# VHDCI_Carrier.net
KiCad netlist of a schematic drawn in Altium Designer
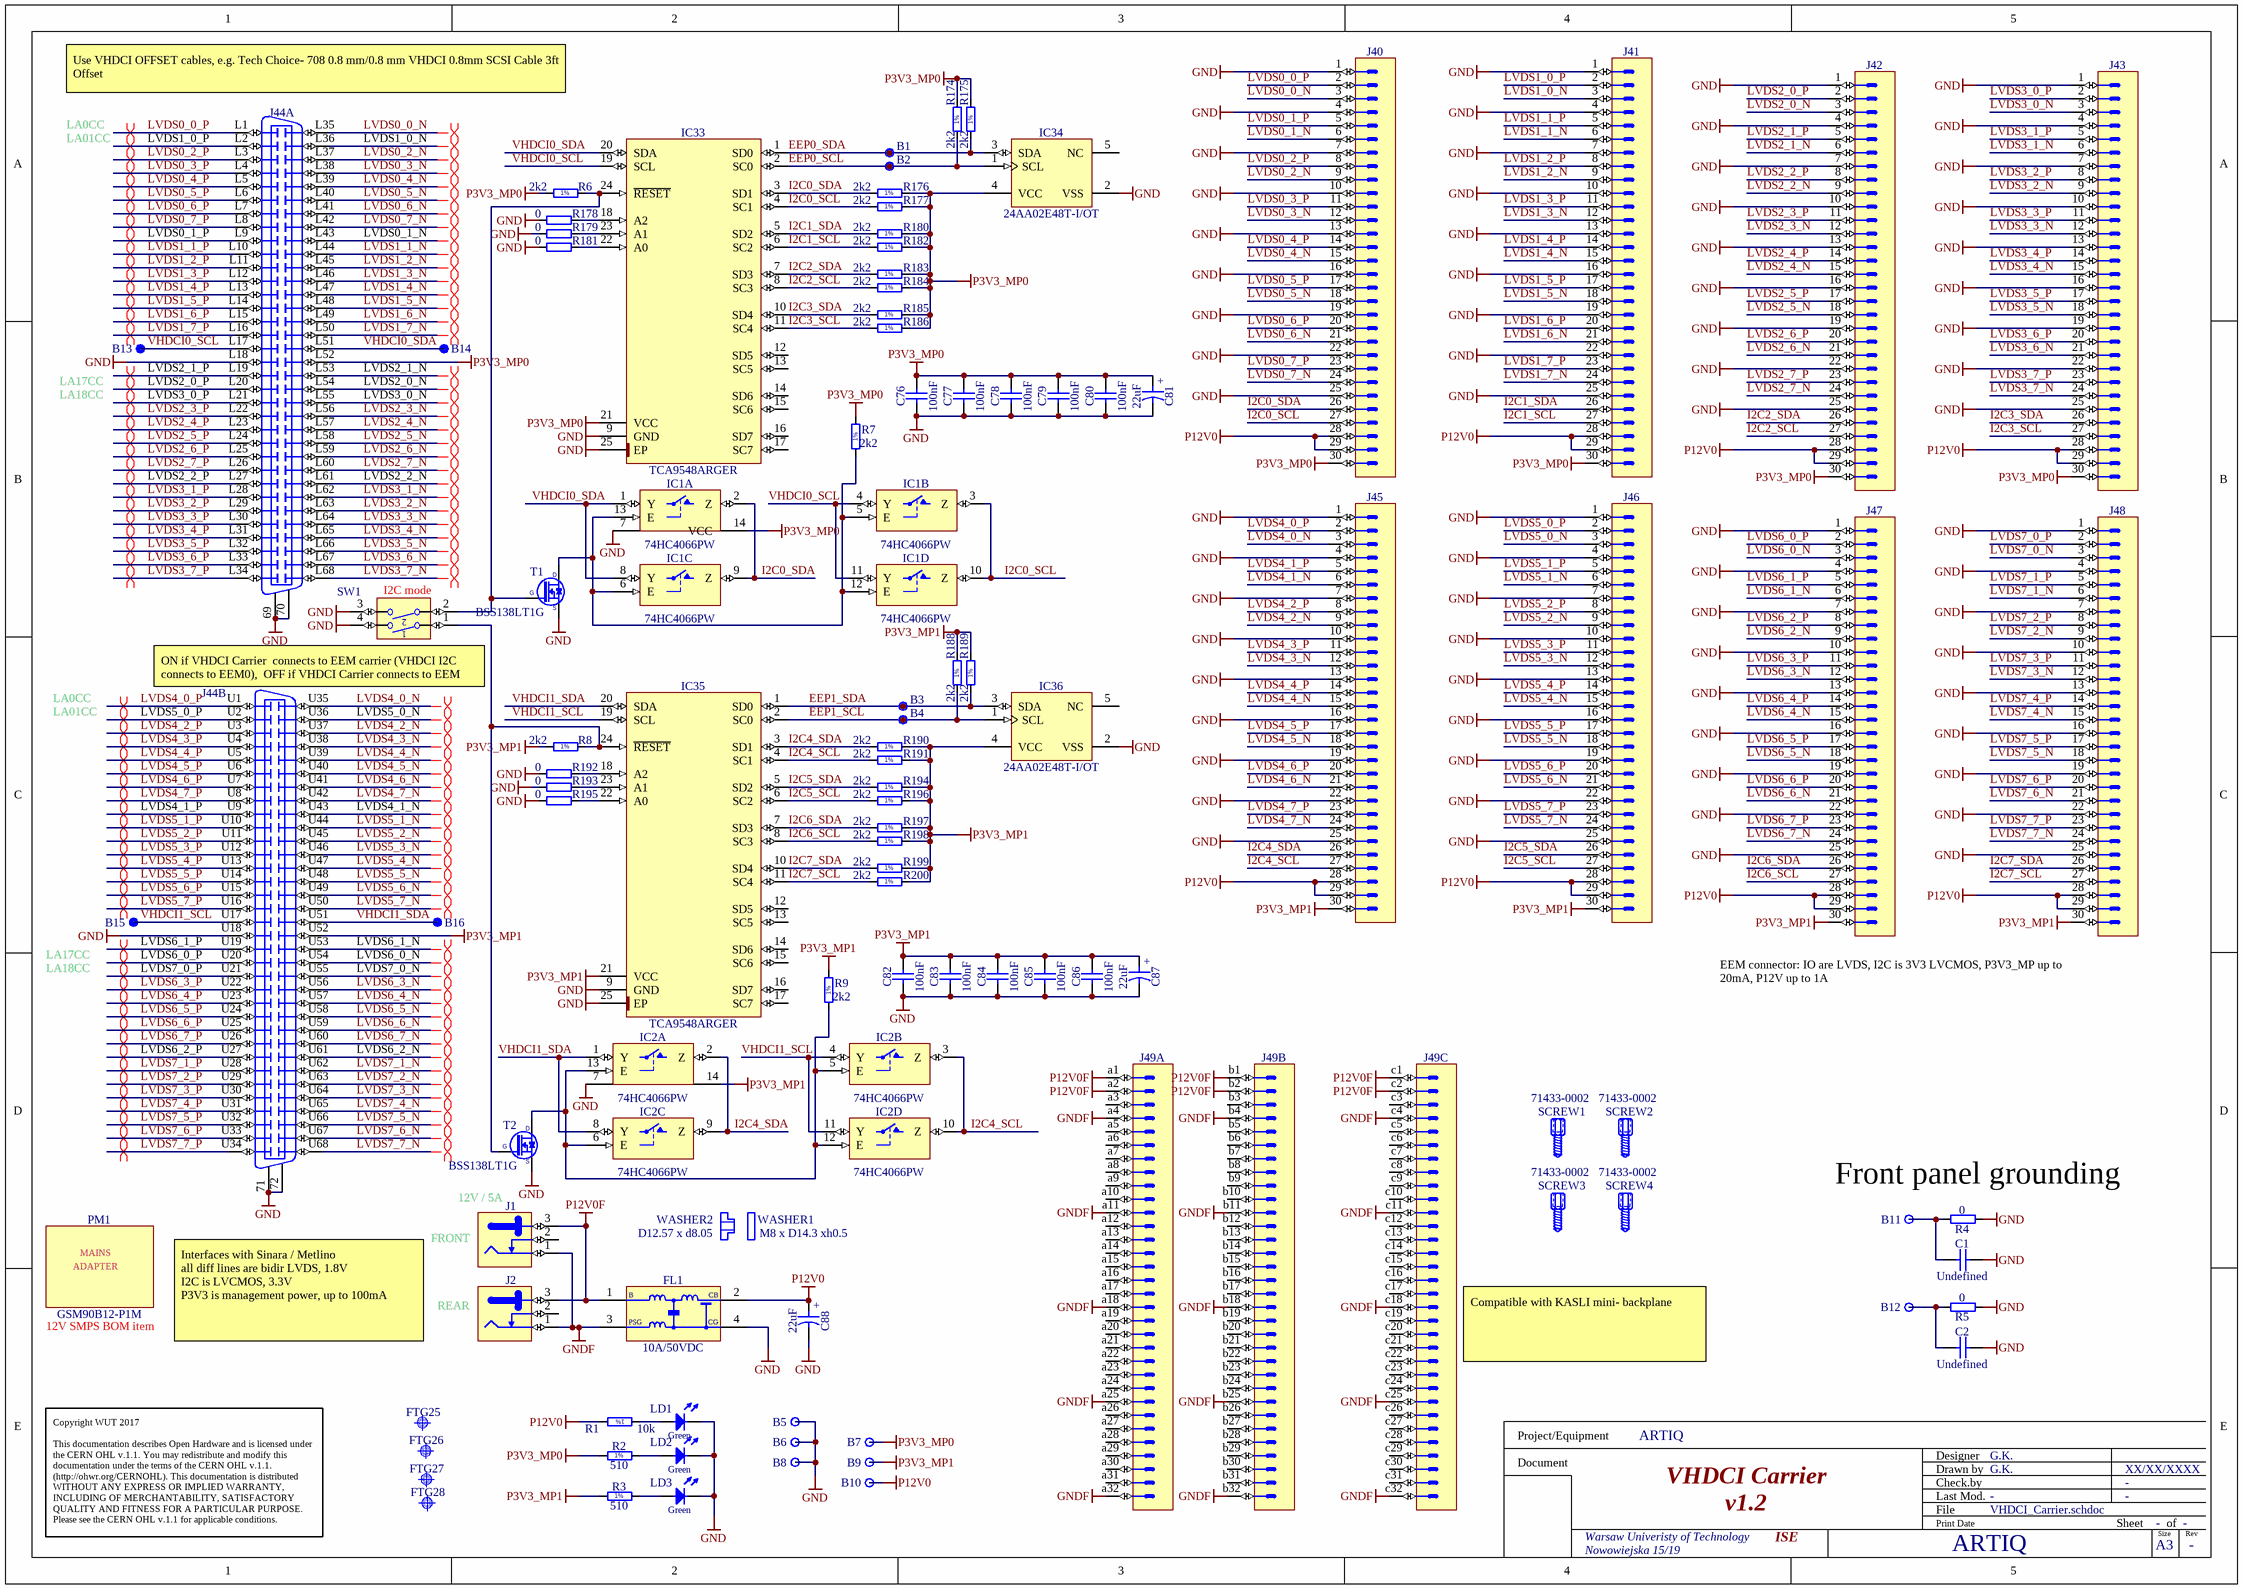
[diagram p0: VHDCI_Carrier.schdoc]

(export (version "E")
  (design (tool "Eeschema 10.0.6"))
  (components
    (comp (ref "B1")
      (value "SMD Pad")
      (footprint "C100")
      (description "Through Hole Pad")
      (fields (field (name "PART NUMBER") "SMD_PAD_D1MM") (field (name "AUTHOR") "CERN DEM JLC"))
      (libsource (lib "Eletro-mechanical") (part "Single SMD Pad (Round)"))
    )
    (comp (ref "B2")
      (value "SMD Pad")
      (footprint "C100")
      (description "Through Hole Pad")
      (fields (field (name "PART NUMBER") "SMD_PAD_D1MM") (field (name "AUTHOR") "CERN DEM JLC"))
      (libsource (lib "Eletro-mechanical") (part "Single SMD Pad (Round)"))
    )
    (comp (ref "B3")
      (value "SMD Pad")
      (footprint "C100")
      (description "Through Hole Pad")
      (fields (field (name "PART NUMBER") "SMD_PAD_D1MM") (field (name "AUTHOR") "CERN DEM JLC"))
      (libsource (lib "Eletro-mechanical") (part "Single SMD Pad (Round)"))
    )
    (comp (ref "B4")
      (value "SMD Pad")
      (footprint "C100")
      (description "Through Hole Pad")
      (fields (field (name "PART NUMBER") "SMD_PAD_D1MM") (field (name "AUTHOR") "CERN DEM JLC"))
      (libsource (lib "Eletro-mechanical") (part "Single SMD Pad (Round)"))
    )
    (comp (ref "B5")
      (value "Plated Hole")
      (footprint "c130h60")
      (description "Single Terminal Socket")
      (fields (field (name "PART NUMBER") "PLATED_HOLE0.6_PAD1.3") (field (name "AUTHOR") "CERN DEM MR"))
      (libsource (lib "Eletro-mechanical") (part "Single Terminal Socket"))
    )
    (comp (ref "B6")
      (value "Plated Hole")
      (footprint "c130h60")
      (description "Single Terminal Socket")
      (fields (field (name "PART NUMBER") "PLATED_HOLE0.6_PAD1.3") (field (name "AUTHOR") "CERN DEM MR"))
      (libsource (lib "Eletro-mechanical") (part "Single Terminal Socket"))
    )
    (comp (ref "B7")
      (value "Plated Hole")
      (footprint "c130h60")
      (description "Single Terminal Socket")
      (fields (field (name "PART NUMBER") "PLATED_HOLE0.6_PAD1.3") (field (name "AUTHOR") "CERN DEM MR"))
      (libsource (lib "Eletro-mechanical") (part "Single Terminal Socket"))
    )
    (comp (ref "B8")
      (value "Plated Hole")
      (footprint "c130h60")
      (description "Single Terminal Socket")
      (fields (field (name "PART NUMBER") "PLATED_HOLE0.6_PAD1.3") (field (name "AUTHOR") "CERN DEM MR"))
      (libsource (lib "Eletro-mechanical") (part "Single Terminal Socket"))
    )
    (comp (ref "B9")
      (value "Plated Hole")
      (footprint "c130h60")
      (description "Single Terminal Socket")
      (fields (field (name "PART NUMBER") "PLATED_HOLE0.6_PAD1.3") (field (name "AUTHOR") "CERN DEM MR"))
      (libsource (lib "Eletro-mechanical") (part "Single Terminal Socket"))
    )
    (comp (ref "B10")
      (value "Plated Hole")
      (footprint "c130h60")
      (description "Single Terminal Socket")
      (fields (field (name "PART NUMBER") "PLATED_HOLE0.6_PAD1.3") (field (name "AUTHOR") "CERN DEM MR"))
      (libsource (lib "Eletro-mechanical") (part "Single Terminal Socket"))
    )
    (comp (ref "B11")
      (value "Plated Hole")
      (footprint "MTG270_500")
      (description "Single Terminal Socket")
      (fields (field (name "PART NUMBER") "PLATED_HOLE2.7_PAD5.0") (field (name "AUTHOR") "CERN DEM JMW"))
      (libsource (lib "Eletro-mechanical") (part "Single Terminal Socket"))
    )
    (comp (ref "B12")
      (value "Plated Hole")
      (footprint "MTG270_500")
      (description "Single Terminal Socket")
      (fields (field (name "PART NUMBER") "PLATED_HOLE2.7_PAD5.0") (field (name "AUTHOR") "CERN DEM JMW"))
      (libsource (lib "Eletro-mechanical") (part "Single Terminal Socket"))
    )
    (comp (ref "B13")
      (value "SMD Pad")
      (footprint "C100")
      (description "Through Hole Pad")
      (fields (field (name "PART NUMBER") "SMD_PAD_D1MM") (field (name "AUTHOR") "CERN DEM JLC"))
      (libsource (lib "Eletro-mechanical") (part "Single SMD Pad (Round)"))
    )
    (comp (ref "B14")
      (value "SMD Pad")
      (footprint "C100")
      (description "Through Hole Pad")
      (fields (field (name "PART NUMBER") "SMD_PAD_D1MM") (field (name "AUTHOR") "CERN DEM JLC"))
      (libsource (lib "Eletro-mechanical") (part "Single SMD Pad (Round)"))
    )
    (comp (ref "B15")
      (value "SMD Pad")
      (footprint "C100")
      (description "Through Hole Pad")
      (fields (field (name "PART NUMBER") "SMD_PAD_D1MM") (field (name "AUTHOR") "CERN DEM JLC"))
      (libsource (lib "Eletro-mechanical") (part "Single SMD Pad (Round)"))
    )
    (comp (ref "B16")
      (value "SMD Pad")
      (footprint "C100")
      (description "Through Hole Pad")
      (fields (field (name "PART NUMBER") "SMD_PAD_D1MM") (field (name "AUTHOR") "CERN DEM JLC"))
      (libsource (lib "Eletro-mechanical") (part "Single SMD Pad (Round)"))
    )
    (comp (ref "C1")
      (value "Undefined")
      (footprint "CAPC2012X135N")
      (description "Non-polarised capacitor")
      (fields (field (name "PART NUMBER") "CC0805_NO-VALUE") (field (name "AUTHOR") "CERN DEM JLC"))
      (libsource (lib "Capacitors") (part "Capacitor - non polarized"))
    )
    (comp (ref "C2")
      (value "Undefined")
      (footprint "CAPC2012X135N")
      (description "Non-polarised capacitor")
      (fields (field (name "PART NUMBER") "CC0805_NO-VALUE") (field (name "AUTHOR") "CERN DEM JLC"))
      (libsource (lib "Capacitors") (part "Capacitor - non polarized"))
    )
    (comp (ref "C76")
      (value "100nF")
      (footprint "CAPC1005X55N")
      (description "Non-polarised capacitor")
      (fields
        (field (name "PART NUMBER") "CC0402_100NF_16V_10%_X5R")
        (field (name "VOLTAGE") "16V")
        (field (name "AUTHOR") "CERN DEM JLC")
      )
      (libsource (lib "Capacitors") (part "Capacitor - non polarized"))
    )
    (comp (ref "C77")
      (value "100nF")
      (footprint "CAPC1005X55N")
      (description "Non-polarised capacitor")
      (fields
        (field (name "PART NUMBER") "CC0402_100NF_16V_10%_X5R")
        (field (name "VOLTAGE") "16V")
        (field (name "AUTHOR") "CERN DEM JLC")
      )
      (libsource (lib "Capacitors") (part "Capacitor - non polarized"))
    )
    (comp (ref "C78")
      (value "100nF")
      (footprint "CAPC1005X55N")
      (description "Non-polarised capacitor")
      (fields
        (field (name "PART NUMBER") "CC0402_100NF_16V_10%_X5R")
        (field (name "VOLTAGE") "16V")
        (field (name "AUTHOR") "CERN DEM JLC")
      )
      (libsource (lib "Capacitors") (part "Capacitor - non polarized"))
    )
    (comp (ref "C79")
      (value "100nF")
      (footprint "CAPC1005X55N")
      (description "Non-polarised capacitor")
      (fields
        (field (name "PART NUMBER") "CC0402_100NF_16V_10%_X5R")
        (field (name "VOLTAGE") "16V")
        (field (name "AUTHOR") "CERN DEM JLC")
      )
      (libsource (lib "Capacitors") (part "Capacitor - non polarized"))
    )
    (comp (ref "C80")
      (value "100nF")
      (footprint "CAPC1005X55N")
      (description "Non-polarised capacitor")
      (fields
        (field (name "PART NUMBER") "CC0402_100NF_16V_10%_X5R")
        (field (name "VOLTAGE") "16V")
        (field (name "AUTHOR") "CERN DEM JLC")
      )
      (libsource (lib "Capacitors") (part "Capacitor - non polarized"))
    )
    (comp (ref "C81")
      (value "22uF")
      (footprint "CAPAE530X540N")
      (description "Polarised capacitor")
      (fields
        (field (name "PART NUMBER") "CAE530-540_22UF_16V_20%")
        (field (name "VOLTAGE") "16V")
        (field (name "AUTHOR") "CERN DEM JLC")
      )
      (libsource (lib "Capacitors") (part "Capacitor - polarized"))
    )
    (comp (ref "C82")
      (value "100nF")
      (footprint "CAPC1005X55N")
      (description "Non-polarised capacitor")
      (fields
        (field (name "PART NUMBER") "CC0402_100NF_16V_10%_X5R")
        (field (name "VOLTAGE") "16V")
        (field (name "AUTHOR") "CERN DEM JLC")
      )
      (libsource (lib "Capacitors") (part "Capacitor - non polarized"))
    )
    (comp (ref "C83")
      (value "100nF")
      (footprint "CAPC1005X55N")
      (description "Non-polarised capacitor")
      (fields
        (field (name "PART NUMBER") "CC0402_100NF_16V_10%_X5R")
        (field (name "VOLTAGE") "16V")
        (field (name "AUTHOR") "CERN DEM JLC")
      )
      (libsource (lib "Capacitors") (part "Capacitor - non polarized"))
    )
    (comp (ref "C84")
      (value "100nF")
      (footprint "CAPC1005X55N")
      (description "Non-polarised capacitor")
      (fields
        (field (name "PART NUMBER") "CC0402_100NF_16V_10%_X5R")
        (field (name "VOLTAGE") "16V")
        (field (name "AUTHOR") "CERN DEM JLC")
      )
      (libsource (lib "Capacitors") (part "Capacitor - non polarized"))
    )
    (comp (ref "C85")
      (value "100nF")
      (footprint "CAPC1005X55N")
      (description "Non-polarised capacitor")
      (fields
        (field (name "PART NUMBER") "CC0402_100NF_16V_10%_X5R")
        (field (name "VOLTAGE") "16V")
        (field (name "AUTHOR") "CERN DEM JLC")
      )
      (libsource (lib "Capacitors") (part "Capacitor - non polarized"))
    )
    (comp (ref "C86")
      (value "100nF")
      (footprint "CAPC1005X55N")
      (description "Non-polarised capacitor")
      (fields
        (field (name "PART NUMBER") "CC0402_100NF_16V_10%_X5R")
        (field (name "VOLTAGE") "16V")
        (field (name "AUTHOR") "CERN DEM JLC")
      )
      (libsource (lib "Capacitors") (part "Capacitor - non polarized"))
    )
    (comp (ref "C87")
      (value "22uF")
      (footprint "CAPAE530X540N")
      (description "Polarised capacitor")
      (fields
        (field (name "PART NUMBER") "CAE530-540_22UF_16V_20%")
        (field (name "VOLTAGE") "16V")
        (field (name "AUTHOR") "CERN DEM JLC")
      )
      (libsource (lib "Capacitors") (part "Capacitor - polarized"))
    )
    (comp (ref "C88")
      (value "22uF")
      (footprint "CAPAE530X540N")
      (description "Polarised capacitor")
      (fields
        (field (name "PART NUMBER") "CAE530-540_22UF_16V_20%")
        (field (name "VOLTAGE") "16V")
        (field (name "AUTHOR") "CERN DEM JLC")
      )
      (libsource (lib "Capacitors") (part "Capacitor - polarized"))
    )
    (comp (ref "FL1")
      (value "10A/50VDC")
      (footprint "FIL_MURATA_BNX02")
      (description "Block Type EMIFIL (LC Combined)")
      (fields
        (field (name "PART NUMBER") "FIL_MURATA_BNX022-01L")
        (field (name "MANUFACTURER") "MURATA")
        (field (name "AUTHOR") "CERN DEM JLC")
      )
      (libsource (lib "Inductors & Transformers") (part "FIL_MURATA_BNX02"))
    )
    (comp (ref "FTG25")
      (value "Use only in PCB")
      (footprint "FIDUCIAL_TOP_C100-200")
      (description "Fiducial Target")
      (fields (field (name "PART NUMBER") "FIDUCIAL_TARGET_C100-200") (field (name "AUTHOR") "CERN DEM JLC"))
      (libsource (lib "Eletro-mechanical") (part "Fiducial Target"))
    )
    (comp (ref "FTG26")
      (value "Use only in PCB")
      (footprint "FIDUCIAL_TOP_S100-200")
      (description "Fiducial Target")
      (fields (field (name "PART NUMBER") "FIDUCIAL_TARGET_S100-200") (field (name "AUTHOR") "CERN DEM JLC"))
      (libsource (lib "Eletro-mechanical") (part "Fiducial Target"))
    )
    (comp (ref "FTG27")
      (value "Use only in PCB")
      (footprint "FIDUCIAL_TOP_S200-400")
      (description "Fiducial Target")
      (fields (field (name "PART NUMBER") "FIDUCIAL_TARGET_S200-400") (field (name "AUTHOR") "CERN DEM JLC"))
      (libsource (lib "Eletro-mechanical") (part "Fiducial Target"))
    )
    (comp (ref "FTG28")
      (value "Use only in PCB")
      (footprint "FIDUCIAL_TOP_S100-200")
      (description "Fiducial Target")
      (fields (field (name "PART NUMBER") "FIDUCIAL_TARGET_S100-200") (field (name "AUTHOR") "CERN DEM JLC"))
      (libsource (lib "Eletro-mechanical") (part "Fiducial Target"))
    )
    (comp (ref "IC1")
      (value "74HC4066PW")
      (footprint "SOP65P640X110-14N")
      (fields (field (name "MANUFACTURER") "NXP SEMICONDUCTORS") (field (name "AUTHOR") "CERN DEM JLC"))
      (libsource (lib "") (part "4066_1"))
    )
    (comp (ref "IC2")
      (value "74HC4066PW")
      (footprint "SOP65P640X110-14N")
      (fields (field (name "MANUFACTURER") "NXP SEMICONDUCTORS") (field (name "AUTHOR") "CERN DEM JLC"))
      (libsource (lib "ICs And Semiconductors") (part "4066"))
    )
    (comp (ref "IC33")
      (value "TCA9548ARGER")
      (footprint "QFN50P400X400X100-25N-S220")
      (description "Low Voltage 8-Channel I2C Switch With Reset")
      (fields (field (name "MANUFACTURER") "TEXAS INSTRUMENTS") (field (name "AUTHOR") "CERN DEM JLC"))
      (libsource (lib "ICs And Semiconductors") (part "TCA9548ARGER"))
    )
    (comp (ref "IC34")
      (value "24AA02E48T-I/OT")
      (footprint "SOT95P280X145-5N")
      (description "1.7V-5.5V, 2K I2C Serial EEPROM With EUI-48 Node Identity")
      (fields (field (name "MANUFACTURER") "MICROCHIP TECHNOLOGY") (field (name "AUTHOR") "CERN DEM MR"))
      (libsource (lib "ICs And Semiconductors") (part "24AA02E48T-I/OT"))
    )
    (comp (ref "IC35")
      (value "TCA9548ARGER")
      (footprint "QFN50P400X400X100-25N-S220")
      (description "Low Voltage 8-Channel I2C Switch With Reset")
      (fields (field (name "MANUFACTURER") "TEXAS INSTRUMENTS") (field (name "AUTHOR") "CERN DEM JLC"))
      (libsource (lib "ICs And Semiconductors") (part "TCA9548ARGER"))
    )
    (comp (ref "IC36")
      (value "24AA02E48T-I/OT")
      (footprint "SOT95P280X145-5N")
      (description "1.7V-5.5V, 2K I2C Serial EEPROM With EUI-48 Node Identity")
      (fields (field (name "MANUFACTURER") "MICROCHIP TECHNOLOGY") (field (name "AUTHOR") "CERN DEM MR"))
      (libsource (lib "ICs And Semiconductors") (part "24AA02E48T-I/OT"))
    )
    (comp (ref "J1")
      (value "Jack")
      (footprint "SWITCHCRAFT_L712RA")
      (description "24V /3. 5A, 2.1mm Diameter Pin, SMD DC Power Supply Connector With  Break Contact")
      (fields
        (field (name "PART NUMBER") "SWITCHCRAFT_L712RA")
        (field (name "MANUFACTURER") "SWITCHCRAFT")
        (field (name "AUTHOR") "GK")
      )
      (libsource (lib "LIBRARY_SCH") (part "CON_DC_5A_THT_RA"))
    )
    (comp (ref "J2")
      (value "Jack")
      (footprint "SWITCHCRAFT_L712RA")
      (description "24V /3. 5A, 2.1mm Diameter Pin, SMD DC Power Supply Connector With  Break Contact")
      (fields
        (field (name "PART NUMBER") "SWITCHCRAFT_L712RA")
        (field (name "MANUFACTURER") "SWITCHCRAFT")
        (field (name "AUTHOR") "GK")
      )
      (libsource (lib "LIBRARY_SCH") (part "CON_DC_5A_THT_RA"))
    )
    (comp (ref "J40")
      (value "~")
      (footprint "3M_N2530-6002RB")
      (description "Connector 30 Male")
      (fields
        (field (name "PART NUMBER") "3M_N2530-6002RB")
        (field (name "MANUFACTURER") "3M")
        (field (name "AUTHOR") "CERN DEM JLC")
      )
      (libsource (lib "Connectors") (part "Connector 30 Male"))
    )
    (comp (ref "J41")
      (value "~")
      (footprint "3M_N2530-6002RB")
      (description "Connector 30 Male")
      (fields
        (field (name "PART NUMBER") "3M_N2530-6002RB")
        (field (name "MANUFACTURER") "3M")
        (field (name "AUTHOR") "CERN DEM JLC")
      )
      (libsource (lib "Connectors") (part "Connector 30 Male"))
    )
    (comp (ref "J42")
      (value "~")
      (footprint "3M_N2530-6002RB")
      (description "Connector 30 Male")
      (fields
        (field (name "PART NUMBER") "3M_N2530-6002RB")
        (field (name "MANUFACTURER") "3M")
        (field (name "AUTHOR") "CERN DEM JLC")
      )
      (libsource (lib "Connectors") (part "Connector 30 Male"))
    )
    (comp (ref "J43")
      (value "~")
      (footprint "3M_N2530-6002RB")
      (description "Connector 30 Male")
      (fields
        (field (name "PART NUMBER") "3M_N2530-6002RB")
        (field (name "MANUFACTURER") "3M")
        (field (name "AUTHOR") "CERN DEM JLC")
      )
      (libsource (lib "Connectors") (part "Connector 30 Male"))
    )
    (comp (ref "J44")
      (value "VHDCI")
      (footprint "MOLEX_74337-0015")
      (description "Very High Density Cable Interconnect (VHDCI ) 2x68 Female")
      (fields
        (field (name "PART NUMBER") "Delivered by GK")
        (field (name "MANUFACTURER") "MOLEX")
        (field (name "AUTHOR") "CERN DEM JLC")
      )
      (libsource (lib "Connectors") (part "Connector VHDCI 2x68 Female"))
    )
    (comp (ref "J45")
      (value "~")
      (footprint "3M_N2530-6002RB")
      (description "Connector 30 Male")
      (fields
        (field (name "PART NUMBER") "3M_N2530-6002RB")
        (field (name "MANUFACTURER") "3M")
        (field (name "AUTHOR") "CERN DEM JLC")
      )
      (libsource (lib "Connectors") (part "Connector 30 Male"))
    )
    (comp (ref "J46")
      (value "~")
      (footprint "3M_N2530-6002RB")
      (description "Connector 30 Male")
      (fields
        (field (name "PART NUMBER") "3M_N2530-6002RB")
        (field (name "MANUFACTURER") "3M")
        (field (name "AUTHOR") "CERN DEM JLC")
      )
      (libsource (lib "Connectors") (part "Connector 30 Male"))
    )
    (comp (ref "J47")
      (value "~")
      (footprint "3M_N2530-6002RB")
      (description "Connector 30 Male")
      (fields
        (field (name "PART NUMBER") "3M_N2530-6002RB")
        (field (name "MANUFACTURER") "3M")
        (field (name "AUTHOR") "CERN DEM JLC")
      )
      (libsource (lib "Connectors") (part "Connector 30 Male"))
    )
    (comp (ref "J48")
      (value "~")
      (footprint "3M_N2530-6002RB")
      (description "Connector 30 Male")
      (fields
        (field (name "PART NUMBER") "3M_N2530-6002RB")
        (field (name "MANUFACTURER") "3M")
        (field (name "AUTHOR") "CERN DEM JLC")
      )
      (libsource (lib "Connectors") (part "Connector 30 Male"))
    )
    (comp (ref "J49")
      (value "DNP")
      (footprint "HARTING_09 03 196 2921")
      (description "Connector 96abc male (3x32)")
      (fields
        (field (name "PART NUMBER") "HARTING_09 03 196 2921")
        (field (name "MANUFACTURER") "HARTING")
        (field (name "AUTHOR") "CERN DEM JLC")
      )
      (libsource (lib "Connectors") (part "Connector 96abc male (3x32)"))
    )
    (comp (ref "LD1")
      (value "Green")
      (footprint "LED_KINGBRIGHT_KPH-1608CGCK")
      (description "LED Green 1C 2A")
      (fields
        (field (name "PART NUMBER") "LED_KINGBRIGHT_KPH-1608CGCK")
        (field (name "MANUFACTURER") "KINGBRIGHT")
        (field (name "AUTHOR") "CERN DEM JLC")
      )
      (libsource (lib "ICs And Semiconductors") (part "LED Green 1C 2A"))
    )
    (comp (ref "LD2")
      (value "Green")
      (footprint "LED_KINGBRIGHT_KPH-1608CGCK")
      (description "LED Green 1C 2A")
      (fields
        (field (name "PART NUMBER") "LED_KINGBRIGHT_KPH-1608CGCK")
        (field (name "MANUFACTURER") "KINGBRIGHT")
        (field (name "AUTHOR") "CERN DEM JLC")
      )
      (libsource (lib "ICs And Semiconductors") (part "LED Green 1C 2A"))
    )
    (comp (ref "LD3")
      (value "Green")
      (footprint "LED_KINGBRIGHT_KPH-1608CGCK")
      (description "LED Green 1C 2A")
      (fields
        (field (name "PART NUMBER") "LED_KINGBRIGHT_KPH-1608CGCK")
        (field (name "MANUFACTURER") "KINGBRIGHT")
        (field (name "AUTHOR") "CERN DEM JLC")
      )
      (libsource (lib "ICs And Semiconductors") (part "LED Green 1C 2A"))
    )
    (comp (ref "PM1")
      (value "GSM90B12-P1M")
      (footprint "DC_DC_GSM90B12-P1M")
      (description "90W  AC-DC  Medical Power Adaptor")
      (fields (field (name "MANUFACTURER") "MEAN WELL") (field (name "AUTHOR") "GK"))
      (libsource (lib "LIBRARY_SCH") (part "DC_DC_GSM90B12-P1M"))
    )
    (comp (ref "R1")
      (value "10k")
      (footprint "RESC1005X40N")
      (description "Resistor - 1%")
      (fields
        (field (name "PART NUMBER") "R0402_10K_1%_0.0625W_100PPM")
        (field (name "POWER") "0.0625W")
        (field (name "AUTHOR") "CERN DEM JLC")
      )
      (libsource (lib "Resistors") (part "Resistor - 1%"))
    )
    (comp (ref "R2")
      (value "510")
      (footprint "RESC1005X40N")
      (description "Resistor - 1%")
      (fields
        (field (name "PART NUMBER") "R0402_510R_1%_0.0625W_100PPM")
        (field (name "POWER") "0.0625W")
        (field (name "AUTHOR") "CERN DEM JLC")
      )
      (libsource (lib "Resistors") (part "Resistor - 1%"))
    )
    (comp (ref "R3")
      (value "510")
      (footprint "RESC1005X40N")
      (description "Resistor - 1%")
      (fields
        (field (name "PART NUMBER") "R0402_510R_1%_0.0625W_100PPM")
        (field (name "POWER") "0.0625W")
        (field (name "AUTHOR") "CERN DEM JLC")
      )
      (libsource (lib "Resistors") (part "Resistor - 1%"))
    )
    (comp (ref "R4")
      (value "0")
      (footprint "RESC1608X55N")
      (description "Resistor")
      (fields
        (field (name "PART NUMBER") "R0603_0R_JUMPER")
        (field (name "MANUFACTURER") "GENERIC")
        (field (name "AUTHOR") "CERN DEM JLC")
      )
      (libsource (lib "Resistors") (part "Resistor"))
    )
    (comp (ref "R5")
      (value "0")
      (footprint "RESC1608X55N")
      (description "Resistor")
      (fields
        (field (name "PART NUMBER") "R0603_0R_JUMPER")
        (field (name "MANUFACTURER") "GENERIC")
        (field (name "AUTHOR") "CERN DEM JLC")
      )
      (libsource (lib "Resistors") (part "Resistor"))
    )
    (comp (ref "R6")
      (value "2k2")
      (footprint "RESC1005X40N")
      (description "Resistor - 1%")
      (fields
        (field (name "PART NUMBER") "R0402_2K2_1%_0.0625W_100PPM")
        (field (name "POWER") "0.0625W")
        (field (name "AUTHOR") "CERN DEM JLC")
      )
      (libsource (lib "Resistors") (part "Resistor - 1%"))
    )
    (comp (ref "R7")
      (value "2k2")
      (footprint "RESC1005X40N")
      (description "Resistor - 1%")
      (fields
        (field (name "PART NUMBER") "R0402_2K2_1%_0.0625W_100PPM")
        (field (name "POWER") "0.0625W")
        (field (name "AUTHOR") "CERN DEM JLC")
      )
      (libsource (lib "Resistors") (part "Resistor - 1%"))
    )
    (comp (ref "R8")
      (value "2k2")
      (footprint "RESC1005X40N")
      (description "Resistor - 1%")
      (fields
        (field (name "PART NUMBER") "R0402_2K2_1%_0.0625W_100PPM")
        (field (name "POWER") "0.0625W")
        (field (name "AUTHOR") "CERN DEM JLC")
      )
      (libsource (lib "Resistors") (part "Resistor - 1%"))
    )
    (comp (ref "R9")
      (value "2k2")
      (footprint "RESC1005X40N")
      (description "Resistor - 1%")
      (fields
        (field (name "PART NUMBER") "R0402_2K2_1%_0.0625W_100PPM")
        (field (name "POWER") "0.0625W")
        (field (name "AUTHOR") "CERN DEM JLC")
      )
      (libsource (lib "Resistors") (part "Resistor - 1%"))
    )
    (comp (ref "R174")
      (value "2k2")
      (footprint "RESC1005X40N")
      (description "Resistor - 1%")
      (fields
        (field (name "PART NUMBER") "R0402_2K2_1%_0.0625W_100PPM")
        (field (name "POWER") "0.0625W")
        (field (name "AUTHOR") "CERN DEM JLC")
      )
      (libsource (lib "Resistors") (part "Resistor - 1%"))
    )
    (comp (ref "R175")
      (value "2k2")
      (footprint "RESC1005X40N")
      (description "Resistor - 1%")
      (fields
        (field (name "PART NUMBER") "R0402_2K2_1%_0.0625W_100PPM")
        (field (name "POWER") "0.0625W")
        (field (name "AUTHOR") "CERN DEM JLC")
      )
      (libsource (lib "Resistors") (part "Resistor - 1%"))
    )
    (comp (ref "R176")
      (value "2k2")
      (footprint "RESC1005X40N")
      (description "Resistor - 1%")
      (fields
        (field (name "PART NUMBER") "R0402_2K2_1%_0.0625W_100PPM")
        (field (name "POWER") "0.0625W")
        (field (name "AUTHOR") "CERN DEM JLC")
      )
      (libsource (lib "Resistors") (part "Resistor - 1%"))
    )
    (comp (ref "R177")
      (value "2k2")
      (footprint "RESC1005X40N")
      (description "Resistor - 1%")
      (fields
        (field (name "PART NUMBER") "R0402_2K2_1%_0.0625W_100PPM")
        (field (name "POWER") "0.0625W")
        (field (name "AUTHOR") "CERN DEM JLC")
      )
      (libsource (lib "Resistors") (part "Resistor - 1%"))
    )
    (comp (ref "R178")
      (value "0")
      (footprint "RESC1005X40N")
      (description "Resistor")
      (fields
        (field (name "PART NUMBER") "R0402_0R_JUMPER")
        (field (name "MANUFACTURER") "GENERIC")
        (field (name "AUTHOR") "CERN DEM JLC")
      )
      (libsource (lib "Resistors") (part "Resistor"))
    )
    (comp (ref "R179")
      (value "0")
      (footprint "RESC1005X40N")
      (description "Resistor")
      (fields
        (field (name "PART NUMBER") "R0402_0R_JUMPER")
        (field (name "MANUFACTURER") "GENERIC")
        (field (name "AUTHOR") "CERN DEM JLC")
      )
      (libsource (lib "Resistors") (part "Resistor"))
    )
    (comp (ref "R180")
      (value "2k2")
      (footprint "RESC1005X40N")
      (description "Resistor - 1%")
      (fields
        (field (name "PART NUMBER") "R0402_2K2_1%_0.0625W_100PPM")
        (field (name "POWER") "0.0625W")
        (field (name "AUTHOR") "CERN DEM JLC")
      )
      (libsource (lib "Resistors") (part "Resistor - 1%"))
    )
    (comp (ref "R181")
      (value "0")
      (footprint "RESC1005X40N")
      (description "Resistor")
      (fields
        (field (name "PART NUMBER") "R0402_0R_JUMPER")
        (field (name "MANUFACTURER") "GENERIC")
        (field (name "AUTHOR") "CERN DEM JLC")
      )
      (libsource (lib "Resistors") (part "Resistor"))
    )
    (comp (ref "R182")
      (value "2k2")
      (footprint "RESC1005X40N")
      (description "Resistor - 1%")
      (fields
        (field (name "PART NUMBER") "R0402_2K2_1%_0.0625W_100PPM")
        (field (name "POWER") "0.0625W")
        (field (name "AUTHOR") "CERN DEM JLC")
      )
      (libsource (lib "Resistors") (part "Resistor - 1%"))
    )
    (comp (ref "R183")
      (value "2k2")
      (footprint "RESC1005X40N")
      (description "Resistor - 1%")
      (fields
        (field (name "PART NUMBER") "R0402_2K2_1%_0.0625W_100PPM")
        (field (name "POWER") "0.0625W")
        (field (name "AUTHOR") "CERN DEM JLC")
      )
      (libsource (lib "Resistors") (part "Resistor - 1%"))
    )
    (comp (ref "R184")
      (value "2k2")
      (footprint "RESC1005X40N")
      (description "Resistor - 1%")
      (fields
        (field (name "PART NUMBER") "R0402_2K2_1%_0.0625W_100PPM")
        (field (name "POWER") "0.0625W")
        (field (name "AUTHOR") "CERN DEM JLC")
      )
      (libsource (lib "Resistors") (part "Resistor - 1%"))
    )
    (comp (ref "R185")
      (value "2k2")
      (footprint "RESC1005X40N")
      (description "Resistor - 1%")
      (fields
        (field (name "PART NUMBER") "R0402_2K2_1%_0.0625W_100PPM")
        (field (name "POWER") "0.0625W")
        (field (name "AUTHOR") "CERN DEM JLC")
      )
      (libsource (lib "Resistors") (part "Resistor - 1%"))
    )
    (comp (ref "R186")
      (value "2k2")
      (footprint "RESC1005X40N")
      (description "Resistor - 1%")
      (fields
        (field (name "PART NUMBER") "R0402_2K2_1%_0.0625W_100PPM")
        (field (name "POWER") "0.0625W")
        (field (name "AUTHOR") "CERN DEM JLC")
      )
      (libsource (lib "Resistors") (part "Resistor - 1%"))
    )
    (comp (ref "R188")
      (value "2k2")
      (footprint "RESC1005X40N")
      (description "Resistor - 1%")
      (fields
        (field (name "PART NUMBER") "R0402_2K2_1%_0.0625W_100PPM")
        (field (name "POWER") "0.0625W")
        (field (name "AUTHOR") "CERN DEM JLC")
      )
      (libsource (lib "Resistors") (part "Resistor - 1%"))
    )
    (comp (ref "R189")
      (value "2k2")
      (footprint "RESC1005X40N")
      (description "Resistor - 1%")
      (fields
        (field (name "PART NUMBER") "R0402_2K2_1%_0.0625W_100PPM")
        (field (name "POWER") "0.0625W")
        (field (name "AUTHOR") "CERN DEM JLC")
      )
      (libsource (lib "Resistors") (part "Resistor - 1%"))
    )
    (comp (ref "R190")
      (value "2k2")
      (footprint "RESC1005X40N")
      (description "Resistor - 1%")
      (fields
        (field (name "PART NUMBER") "R0402_2K2_1%_0.0625W_100PPM")
        (field (name "POWER") "0.0625W")
        (field (name "AUTHOR") "CERN DEM JLC")
      )
      (libsource (lib "Resistors") (part "Resistor - 1%"))
    )
    (comp (ref "R191")
      (value "2k2")
      (footprint "RESC1005X40N")
      (description "Resistor - 1%")
      (fields
        (field (name "PART NUMBER") "R0402_2K2_1%_0.0625W_100PPM")
        (field (name "POWER") "0.0625W")
        (field (name "AUTHOR") "CERN DEM JLC")
      )
      (libsource (lib "Resistors") (part "Resistor - 1%"))
    )
    (comp (ref "R192")
      (value "0")
      (footprint "RESC1005X40N")
      (description "Resistor")
      (fields
        (field (name "PART NUMBER") "R0402_0R_JUMPER")
        (field (name "MANUFACTURER") "GENERIC")
        (field (name "AUTHOR") "CERN DEM JLC")
      )
      (libsource (lib "Resistors") (part "Resistor"))
    )
    (comp (ref "R193")
      (value "0")
      (footprint "RESC1005X40N")
      (description "Resistor")
      (fields
        (field (name "PART NUMBER") "R0402_0R_JUMPER")
        (field (name "MANUFACTURER") "GENERIC")
        (field (name "AUTHOR") "CERN DEM JLC")
      )
      (libsource (lib "Resistors") (part "Resistor"))
    )
    (comp (ref "R194")
      (value "2k2")
      (footprint "RESC1005X40N")
      (description "Resistor - 1%")
      (fields
        (field (name "PART NUMBER") "R0402_2K2_1%_0.0625W_100PPM")
        (field (name "POWER") "0.0625W")
        (field (name "AUTHOR") "CERN DEM JLC")
      )
      (libsource (lib "Resistors") (part "Resistor - 1%"))
    )
    (comp (ref "R195")
      (value "0")
      (footprint "RESC1005X40N")
      (description "Resistor")
      (fields
        (field (name "PART NUMBER") "R0402_0R_JUMPER")
        (field (name "MANUFACTURER") "GENERIC")
        (field (name "AUTHOR") "CERN DEM JLC")
      )
      (libsource (lib "Resistors") (part "Resistor"))
    )
    (comp (ref "R196")
      (value "2k2")
      (footprint "RESC1005X40N")
      (description "Resistor - 1%")
      (fields
        (field (name "PART NUMBER") "R0402_2K2_1%_0.0625W_100PPM")
        (field (name "POWER") "0.0625W")
        (field (name "AUTHOR") "CERN DEM JLC")
      )
      (libsource (lib "Resistors") (part "Resistor - 1%"))
    )
    (comp (ref "R197")
      (value "2k2")
      (footprint "RESC1005X40N")
      (description "Resistor - 1%")
      (fields
        (field (name "PART NUMBER") "R0402_2K2_1%_0.0625W_100PPM")
        (field (name "POWER") "0.0625W")
        (field (name "AUTHOR") "CERN DEM JLC")
      )
      (libsource (lib "Resistors") (part "Resistor - 1%"))
    )
    (comp (ref "R198")
      (value "2k2")
      (footprint "RESC1005X40N")
      (description "Resistor - 1%")
      (fields
        (field (name "PART NUMBER") "R0402_2K2_1%_0.0625W_100PPM")
        (field (name "POWER") "0.0625W")
        (field (name "AUTHOR") "CERN DEM JLC")
      )
      (libsource (lib "Resistors") (part "Resistor - 1%"))
    )
    (comp (ref "R199")
      (value "2k2")
      (footprint "RESC1005X40N")
      (description "Resistor - 1%")
      (fields
        (field (name "PART NUMBER") "R0402_2K2_1%_0.0625W_100PPM")
        (field (name "POWER") "0.0625W")
        (field (name "AUTHOR") "CERN DEM JLC")
      )
      (libsource (lib "Resistors") (part "Resistor - 1%"))
    )
    (comp (ref "R200")
      (value "2k2")
      (footprint "RESC1005X40N")
      (description "Resistor - 1%")
      (fields
        (field (name "PART NUMBER") "R0402_2K2_1%_0.0625W_100PPM")
        (field (name "POWER") "0.0625W")
        (field (name "AUTHOR") "CERN DEM JLC")
      )
      (libsource (lib "Resistors") (part "Resistor - 1%"))
    )
    (comp (ref "SCREW1")
      (value "71433-0002")
      (footprint "MOLEX_71433-0002")
      (description "VHDCI Female Screw Lock")
      (fields
        (field (name "PART NUMBER") "MOLEX_71433-0002")
        (field (name "MANUFACTURER") "Molex")
        (field (name "AUTHOR") "GK")
      )
      (libsource (lib "LIBRARY_SCH") (part "MECH_VHDCI_screw_lock"))
    )
    (comp (ref "SCREW2")
      (value "71433-0002")
      (footprint "MOLEX_71433-0002")
      (description "VHDCI Female Screw Lock")
      (fields
        (field (name "PART NUMBER") "MOLEX_71433-0002")
        (field (name "MANUFACTURER") "Molex")
        (field (name "AUTHOR") "GK")
      )
      (libsource (lib "LIBRARY_SCH") (part "MECH_VHDCI_screw_lock"))
    )
    (comp (ref "SCREW3")
      (value "71433-0002")
      (footprint "MOLEX_71433-0002")
      (description "VHDCI Female Screw Lock")
      (fields
        (field (name "PART NUMBER") "MOLEX_71433-0002")
        (field (name "MANUFACTURER") "Molex")
        (field (name "AUTHOR") "GK")
      )
      (libsource (lib "LIBRARY_SCH") (part "MECH_VHDCI_screw_lock"))
    )
    (comp (ref "SCREW4")
      (value "71433-0002")
      (footprint "MOLEX_71433-0002")
      (description "VHDCI Female Screw Lock")
      (fields
        (field (name "PART NUMBER") "MOLEX_71433-0002")
        (field (name "MANUFACTURER") "Molex")
        (field (name "AUTHOR") "GK")
      )
      (libsource (lib "LIBRARY_SCH") (part "MECH_VHDCI_screw_lock"))
    )
    (comp (ref "SW1")
      (value "Switch")
      (footprint "SW_TYCO_1571983-1")
      (description "2 Ways SPST DIP Switch")
      (fields
        (field (name "PART NUMBER") "SW_TYCO_1571983-1")
        (field (name "MANUFACTURER") "TYCO")
        (field (name "AUTHOR") "CERN DEM JLC")
      )
      (libsource (lib "Eletro-mechanical") (part "SW 2x SPST DIP Switch"))
    )
    (comp (ref "T1")
      (value "BSS138LT1G")
      (footprint "SOT95P240X110-3N")
      (description "N-CHANNEL MOSFET WITH DIODE")
      (fields (field (name "MANUFACTURER") "ON SEMICONDUCTOR") (field (name "AUTHOR") "CERN DEM JLC"))
      (libsource (lib "ICs And Semiconductors") (part "N-MOSFET-D 1G 2S 3D"))
    )
    (comp (ref "T2")
      (value "BSS138LT1G")
      (footprint "SOT95P240X110-3N")
      (description "N-CHANNEL MOSFET WITH DIODE")
      (fields (field (name "MANUFACTURER") "ON SEMICONDUCTOR") (field (name "AUTHOR") "CERN DEM JLC"))
      (libsource (lib "ICs And Semiconductors") (part "N-MOSFET-D 1G 2S 3D"))
    )
    (comp (ref "WASHER1")
      (value "M8 x D14.3 xh0.5")
      (footprint "Washer_M8x0.5x14.3")
      (description "M8 x0.5x14.3 Nylon Washer")
      (fields
        (field (name "PART NUMBER") "WS-M 8-0.5(14.3)")
        (field (name "MANUFACTURER") "ADSYS ELEMENTY")
        (field (name "AUTHOR") "GK")
      )
      (libsource (lib "LIBRARY_SCH") (part "MECH_Washer_M8x0.5x14.3"))
    )
    (comp (ref "WASHER2")
      (value "D12.57 x d8.05")
      (footprint "Washer_s4263")
      (description "8mm_Shoulder Washer")
      (fields
        (field (name "PART NUMBER") "Switchcraft_s4263")
        (field (name "MANUFACTURER") "Switchcraft")
        (field (name "AUTHOR") "GK")
      )
      (libsource (lib "LIBRARY_SCH") (part "MECH_Washer_s4263"))
    )
  )
  (nets
    (net (code "1") (name "/EEP0_SCL") (class "Default")
      (node (ref "B2") (pin "1") (pinfunction "1_1") (pintype "bidirectional"))
      (node (ref "IC33") (pin "2") (pinfunction "SC0_2") (pintype "bidirectional"))
      (node (ref "IC34") (pin "1") (pinfunction "SCL_1") (pintype "input"))
      (node (ref "R174") (pin "1") (pinfunction "1_1") (pintype "passive"))
    )
    (net (code "2") (name "/EEP0_SDA") (class "Default")
      (node (ref "B1") (pin "1") (pinfunction "1_1") (pintype "bidirectional"))
      (node (ref "IC33") (pin "1") (pinfunction "SD0_1") (pintype "bidirectional"))
      (node (ref "IC34") (pin "3") (pinfunction "SDA_3") (pintype "bidirectional"))
      (node (ref "R175") (pin "1") (pinfunction "1_1") (pintype "passive"))
    )
    (net (code "3") (name "/EEP1_SCL") (class "Default")
      (node (ref "B4") (pin "1") (pinfunction "1_1") (pintype "bidirectional"))
      (node (ref "IC35") (pin "2") (pinfunction "SC0_2") (pintype "bidirectional"))
      (node (ref "IC36") (pin "1") (pinfunction "SCL_1") (pintype "input"))
      (node (ref "R188") (pin "1") (pinfunction "1_1") (pintype "passive"))
    )
    (net (code "4") (name "/EEP1_SDA") (class "Default")
      (node (ref "B3") (pin "1") (pinfunction "1_1") (pintype "bidirectional"))
      (node (ref "IC35") (pin "1") (pinfunction "SD0_1") (pintype "bidirectional"))
      (node (ref "IC36") (pin "3") (pinfunction "SDA_3") (pintype "bidirectional"))
      (node (ref "R189") (pin "1") (pinfunction "1_1") (pintype "passive"))
    )
    (net (code "5") (name "/I2C0_SCL") (class "Default")
      (node (ref "IC1") (pin "10") (pinfunction "Z_10") (pintype "bidirectional"))
      (node (ref "IC1") (pin "3") (pinfunction "Z_3") (pintype "bidirectional"))
      (node (ref "IC33") (pin "4") (pinfunction "SC1_4") (pintype "bidirectional"))
      (node (ref "J40") (pin "27") (pinfunction "27_27") (pintype "bidirectional"))
      (node (ref "R177") (pin "1") (pinfunction "1_1") (pintype "passive"))
    )
    (net (code "6") (name "/I2C0_SDA") (class "Default")
      (node (ref "IC1") (pin "2") (pinfunction "Z_2") (pintype "bidirectional"))
      (node (ref "IC1") (pin "9") (pinfunction "Z_9") (pintype "bidirectional"))
      (node (ref "IC33") (pin "3") (pinfunction "SD1_3") (pintype "bidirectional"))
      (node (ref "J40") (pin "26") (pinfunction "26_26") (pintype "bidirectional"))
      (node (ref "R176") (pin "1") (pinfunction "1_1") (pintype "passive"))
    )
    (net (code "7") (name "/I2C1_SCL") (class "Default")
      (node (ref "IC33") (pin "6") (pinfunction "SC2_6") (pintype "bidirectional"))
      (node (ref "J41") (pin "27") (pinfunction "27_27") (pintype "bidirectional"))
      (node (ref "R182") (pin "1") (pinfunction "1_1") (pintype "passive"))
    )
    (net (code "8") (name "/I2C1_SDA") (class "Default")
      (node (ref "IC33") (pin "5") (pinfunction "SD2_5") (pintype "bidirectional"))
      (node (ref "J41") (pin "26") (pinfunction "26_26") (pintype "bidirectional"))
      (node (ref "R180") (pin "1") (pinfunction "1_1") (pintype "passive"))
    )
    (net (code "9") (name "/I2C2_SCL") (class "Default")
      (node (ref "IC33") (pin "8") (pinfunction "SC3_8") (pintype "bidirectional"))
      (node (ref "J42") (pin "27") (pinfunction "27_27") (pintype "bidirectional"))
      (node (ref "R184") (pin "1") (pinfunction "1_1") (pintype "passive"))
    )
    (net (code "10") (name "/I2C2_SDA") (class "Default")
      (node (ref "IC33") (pin "7") (pinfunction "SD3_7") (pintype "bidirectional"))
      (node (ref "J42") (pin "26") (pinfunction "26_26") (pintype "bidirectional"))
      (node (ref "R183") (pin "1") (pinfunction "1_1") (pintype "passive"))
    )
    (net (code "11") (name "/I2C3_SCL") (class "Default")
      (node (ref "IC33") (pin "11") (pinfunction "SC4_11") (pintype "bidirectional"))
      (node (ref "J43") (pin "27") (pinfunction "27_27") (pintype "bidirectional"))
      (node (ref "R186") (pin "1") (pinfunction "1_1") (pintype "passive"))
    )
    (net (code "12") (name "/I2C3_SDA") (class "Default")
      (node (ref "IC33") (pin "10") (pinfunction "SD4_10") (pintype "bidirectional"))
      (node (ref "J43") (pin "26") (pinfunction "26_26") (pintype "bidirectional"))
      (node (ref "R185") (pin "1") (pinfunction "1_1") (pintype "passive"))
    )
    (net (code "13") (name "/I2C4_SCL") (class "Default")
      (node (ref "IC2") (pin "10") (pinfunction "Z_10") (pintype "bidirectional"))
      (node (ref "IC2") (pin "3") (pinfunction "Z_3") (pintype "bidirectional"))
      (node (ref "IC35") (pin "4") (pinfunction "SC1_4") (pintype "bidirectional"))
      (node (ref "J45") (pin "27") (pinfunction "27_27") (pintype "bidirectional"))
      (node (ref "R191") (pin "1") (pinfunction "1_1") (pintype "passive"))
    )
    (net (code "14") (name "/I2C4_SDA") (class "Default")
      (node (ref "IC2") (pin "2") (pinfunction "Z_2") (pintype "bidirectional"))
      (node (ref "IC2") (pin "9") (pinfunction "Z_9") (pintype "bidirectional"))
      (node (ref "IC35") (pin "3") (pinfunction "SD1_3") (pintype "bidirectional"))
      (node (ref "J45") (pin "26") (pinfunction "26_26") (pintype "bidirectional"))
      (node (ref "R190") (pin "1") (pinfunction "1_1") (pintype "passive"))
    )
    (net (code "15") (name "/I2C5_SCL") (class "Default")
      (node (ref "IC35") (pin "6") (pinfunction "SC2_6") (pintype "bidirectional"))
      (node (ref "J46") (pin "27") (pinfunction "27_27") (pintype "bidirectional"))
      (node (ref "R196") (pin "1") (pinfunction "1_1") (pintype "passive"))
    )
    (net (code "16") (name "/I2C5_SDA") (class "Default")
      (node (ref "IC35") (pin "5") (pinfunction "SD2_5") (pintype "bidirectional"))
      (node (ref "J46") (pin "26") (pinfunction "26_26") (pintype "bidirectional"))
      (node (ref "R194") (pin "1") (pinfunction "1_1") (pintype "passive"))
    )
    (net (code "17") (name "/I2C6_SCL") (class "Default")
      (node (ref "IC35") (pin "8") (pinfunction "SC3_8") (pintype "bidirectional"))
      (node (ref "J47") (pin "27") (pinfunction "27_27") (pintype "bidirectional"))
      (node (ref "R198") (pin "1") (pinfunction "1_1") (pintype "passive"))
    )
    (net (code "18") (name "/I2C6_SDA") (class "Default")
      (node (ref "IC35") (pin "7") (pinfunction "SD3_7") (pintype "bidirectional"))
      (node (ref "J47") (pin "26") (pinfunction "26_26") (pintype "bidirectional"))
      (node (ref "R197") (pin "1") (pinfunction "1_1") (pintype "passive"))
    )
    (net (code "19") (name "/I2C7_SCL") (class "Default")
      (node (ref "IC35") (pin "11") (pinfunction "SC4_11") (pintype "bidirectional"))
      (node (ref "J48") (pin "27") (pinfunction "27_27") (pintype "bidirectional"))
      (node (ref "R200") (pin "1") (pinfunction "1_1") (pintype "passive"))
    )
    (net (code "20") (name "/I2C7_SDA") (class "Default")
      (node (ref "IC35") (pin "10") (pinfunction "SD4_10") (pintype "bidirectional"))
      (node (ref "J48") (pin "26") (pinfunction "26_26") (pintype "bidirectional"))
      (node (ref "R199") (pin "1") (pinfunction "1_1") (pintype "passive"))
    )
    (net (code "21") (name "/LVDS0_0_N") (class "Default")
      (node (ref "J40") (pin "3") (pinfunction "3_3") (pintype "bidirectional"))
      (node (ref "J44") (pin "L35") (pinfunction "35_L35") (pintype "bidirectional"))
    )
    (net (code "22") (name "/LVDS0_0_P") (class "Default")
      (node (ref "J40") (pin "2") (pinfunction "2_2") (pintype "bidirectional"))
      (node (ref "J44") (pin "L1") (pinfunction "1_L1") (pintype "bidirectional"))
    )
    (net (code "23") (name "/LVDS0_1_N") (class "Default")
      (node (ref "J40") (pin "6") (pinfunction "6_6") (pintype "bidirectional"))
      (node (ref "J44") (pin "L43") (pinfunction "43_L43") (pintype "bidirectional"))
    )
    (net (code "24") (name "/LVDS0_1_P") (class "Default")
      (node (ref "J40") (pin "5") (pinfunction "5_5") (pintype "bidirectional"))
      (node (ref "J44") (pin "L9") (pinfunction "9_L9") (pintype "bidirectional"))
    )
    (net (code "25") (name "/LVDS0_2_N") (class "Default")
      (node (ref "J40") (pin "9") (pinfunction "9_9") (pintype "bidirectional"))
      (node (ref "J44") (pin "L37") (pinfunction "37_L37") (pintype "bidirectional"))
    )
    (net (code "26") (name "/LVDS0_2_P") (class "Default")
      (node (ref "J40") (pin "8") (pinfunction "8_8") (pintype "bidirectional"))
      (node (ref "J44") (pin "L3") (pinfunction "3_L3") (pintype "bidirectional"))
    )
    (net (code "27") (name "/LVDS0_3_N") (class "Default")
      (node (ref "J40") (pin "12") (pinfunction "12_12") (pintype "bidirectional"))
      (node (ref "J44") (pin "L38") (pinfunction "38_L38") (pintype "bidirectional"))
    )
    (net (code "28") (name "/LVDS0_3_P") (class "Default")
      (node (ref "J40") (pin "11") (pinfunction "11_11") (pintype "bidirectional"))
      (node (ref "J44") (pin "L4") (pinfunction "4_L4") (pintype "bidirectional"))
    )
    (net (code "29") (name "/LVDS0_4_N") (class "Default")
      (node (ref "J40") (pin "15") (pinfunction "15_15") (pintype "bidirectional"))
      (node (ref "J44") (pin "L39") (pinfunction "39_L39") (pintype "bidirectional"))
    )
    (net (code "30") (name "/LVDS0_4_P") (class "Default")
      (node (ref "J40") (pin "14") (pinfunction "14_14") (pintype "bidirectional"))
      (node (ref "J44") (pin "L5") (pinfunction "5_L5") (pintype "bidirectional"))
    )
    (net (code "31") (name "/LVDS0_5_N") (class "Default")
      (node (ref "J40") (pin "18") (pinfunction "18_18") (pintype "bidirectional"))
      (node (ref "J44") (pin "L40") (pinfunction "40_L40") (pintype "bidirectional"))
    )
    (net (code "32") (name "/LVDS0_5_P") (class "Default")
      (node (ref "J40") (pin "17") (pinfunction "17_17") (pintype "bidirectional"))
      (node (ref "J44") (pin "L6") (pinfunction "6_L6") (pintype "bidirectional"))
    )
    (net (code "33") (name "/LVDS0_6_N") (class "Default")
      (node (ref "J40") (pin "21") (pinfunction "21_21") (pintype "bidirectional"))
      (node (ref "J44") (pin "L41") (pinfunction "41_L41") (pintype "bidirectional"))
    )
    (net (code "34") (name "/LVDS0_6_P") (class "Default")
      (node (ref "J40") (pin "20") (pinfunction "20_20") (pintype "bidirectional"))
      (node (ref "J44") (pin "L7") (pinfunction "7_L7") (pintype "bidirectional"))
    )
    (net (code "35") (name "/LVDS0_7_N") (class "Default")
      (node (ref "J40") (pin "24") (pinfunction "24_24") (pintype "bidirectional"))
      (node (ref "J44") (pin "L42") (pinfunction "42_L42") (pintype "bidirectional"))
    )
    (net (code "36") (name "/LVDS0_7_P") (class "Default")
      (node (ref "J40") (pin "23") (pinfunction "23_23") (pintype "bidirectional"))
      (node (ref "J44") (pin "L8") (pinfunction "8_L8") (pintype "bidirectional"))
    )
    (net (code "37") (name "/LVDS1_0_N") (class "Default")
      (node (ref "J41") (pin "3") (pinfunction "3_3") (pintype "bidirectional"))
      (node (ref "J44") (pin "L36") (pinfunction "36_L36") (pintype "bidirectional"))
    )
    (net (code "38") (name "/LVDS1_0_P") (class "Default")
      (node (ref "J41") (pin "2") (pinfunction "2_2") (pintype "bidirectional"))
      (node (ref "J44") (pin "L2") (pinfunction "2_L2") (pintype "bidirectional"))
    )
    (net (code "39") (name "/LVDS1_1_N") (class "Default")
      (node (ref "J41") (pin "6") (pinfunction "6_6") (pintype "bidirectional"))
      (node (ref "J44") (pin "L44") (pinfunction "44_L44") (pintype "bidirectional"))
    )
    (net (code "40") (name "/LVDS1_1_P") (class "Default")
      (node (ref "J41") (pin "5") (pinfunction "5_5") (pintype "bidirectional"))
      (node (ref "J44") (pin "L10") (pinfunction "10_L10") (pintype "bidirectional"))
    )
    (net (code "41") (name "/LVDS1_2_N") (class "Default")
      (node (ref "J41") (pin "9") (pinfunction "9_9") (pintype "bidirectional"))
      (node (ref "J44") (pin "L45") (pinfunction "45_L45") (pintype "bidirectional"))
    )
    (net (code "42") (name "/LVDS1_2_P") (class "Default")
      (node (ref "J41") (pin "8") (pinfunction "8_8") (pintype "bidirectional"))
      (node (ref "J44") (pin "L11") (pinfunction "11_L11") (pintype "bidirectional"))
    )
    (net (code "43") (name "/LVDS1_3_N") (class "Default")
      (node (ref "J41") (pin "12") (pinfunction "12_12") (pintype "bidirectional"))
      (node (ref "J44") (pin "L46") (pinfunction "46_L46") (pintype "bidirectional"))
    )
    (net (code "44") (name "/LVDS1_3_P") (class "Default")
      (node (ref "J41") (pin "11") (pinfunction "11_11") (pintype "bidirectional"))
      (node (ref "J44") (pin "L12") (pinfunction "12_L12") (pintype "bidirectional"))
    )
    (net (code "45") (name "/LVDS1_4_N") (class "Default")
      (node (ref "J41") (pin "15") (pinfunction "15_15") (pintype "bidirectional"))
      (node (ref "J44") (pin "L47") (pinfunction "47_L47") (pintype "bidirectional"))
    )
    (net (code "46") (name "/LVDS1_4_P") (class "Default")
      (node (ref "J41") (pin "14") (pinfunction "14_14") (pintype "bidirectional"))
      (node (ref "J44") (pin "L13") (pinfunction "13_L13") (pintype "bidirectional"))
    )
    (net (code "47") (name "/LVDS1_5_N") (class "Default")
      (node (ref "J41") (pin "18") (pinfunction "18_18") (pintype "bidirectional"))
      (node (ref "J44") (pin "L48") (pinfunction "48_L48") (pintype "bidirectional"))
    )
    (net (code "48") (name "/LVDS1_5_P") (class "Default")
      (node (ref "J41") (pin "17") (pinfunction "17_17") (pintype "bidirectional"))
      (node (ref "J44") (pin "L14") (pinfunction "14_L14") (pintype "bidirectional"))
    )
    (net (code "49") (name "/LVDS1_6_N") (class "Default")
      (node (ref "J41") (pin "21") (pinfunction "21_21") (pintype "bidirectional"))
      (node (ref "J44") (pin "L49") (pinfunction "49_L49") (pintype "bidirectional"))
    )
    (net (code "50") (name "/LVDS1_6_P") (class "Default")
      (node (ref "J41") (pin "20") (pinfunction "20_20") (pintype "bidirectional"))
      (node (ref "J44") (pin "L15") (pinfunction "15_L15") (pintype "bidirectional"))
    )
    (net (code "51") (name "/LVDS1_7_N") (class "Default")
      (node (ref "J41") (pin "24") (pinfunction "24_24") (pintype "bidirectional"))
      (node (ref "J44") (pin "L50") (pinfunction "50_L50") (pintype "bidirectional"))
    )
    (net (code "52") (name "/LVDS1_7_P") (class "Default")
      (node (ref "J41") (pin "23") (pinfunction "23_23") (pintype "bidirectional"))
      (node (ref "J44") (pin "L16") (pinfunction "16_L16") (pintype "bidirectional"))
    )
    (net (code "53") (name "/LVDS2_0_N") (class "Default")
      (node (ref "J42") (pin "3") (pinfunction "3_3") (pintype "bidirectional"))
      (node (ref "J44") (pin "L54") (pinfunction "54_L54") (pintype "bidirectional"))
    )
    (net (code "54") (name "/LVDS2_0_P") (class "Default")
      (node (ref "J42") (pin "2") (pinfunction "2_2") (pintype "bidirectional"))
      (node (ref "J44") (pin "L20") (pinfunction "20_L20") (pintype "bidirectional"))
    )
    (net (code "55") (name "/LVDS2_1_N") (class "Default")
      (node (ref "J42") (pin "6") (pinfunction "6_6") (pintype "bidirectional"))
      (node (ref "J44") (pin "L53") (pinfunction "53_L53") (pintype "bidirectional"))
    )
    (net (code "56") (name "/LVDS2_1_P") (class "Default")
      (node (ref "J42") (pin "5") (pinfunction "5_5") (pintype "bidirectional"))
      (node (ref "J44") (pin "L19") (pinfunction "19_L19") (pintype "bidirectional"))
    )
    (net (code "57") (name "/LVDS2_2_N") (class "Default")
      (node (ref "J42") (pin "9") (pinfunction "9_9") (pintype "bidirectional"))
      (node (ref "J44") (pin "L61") (pinfunction "61_L61") (pintype "bidirectional"))
    )
    (net (code "58") (name "/LVDS2_2_P") (class "Default")
      (node (ref "J42") (pin "8") (pinfunction "8_8") (pintype "bidirectional"))
      (node (ref "J44") (pin "L27") (pinfunction "27_L27") (pintype "bidirectional"))
    )
    (net (code "59") (name "/LVDS2_3_N") (class "Default")
      (node (ref "J42") (pin "12") (pinfunction "12_12") (pintype "bidirectional"))
      (node (ref "J44") (pin "L56") (pinfunction "56_L56") (pintype "bidirectional"))
    )
    (net (code "60") (name "/LVDS2_3_P") (class "Default")
      (node (ref "J42") (pin "11") (pinfunction "11_11") (pintype "bidirectional"))
      (node (ref "J44") (pin "L22") (pinfunction "22_L22") (pintype "bidirectional"))
    )
    (net (code "61") (name "/LVDS2_4_N") (class "Default")
      (node (ref "J42") (pin "15") (pinfunction "15_15") (pintype "bidirectional"))
      (node (ref "J44") (pin "L57") (pinfunction "57_L57") (pintype "bidirectional"))
    )
    (net (code "62") (name "/LVDS2_4_P") (class "Default")
      (node (ref "J42") (pin "14") (pinfunction "14_14") (pintype "bidirectional"))
      (node (ref "J44") (pin "L23") (pinfunction "23_L23") (pintype "bidirectional"))
    )
    (net (code "63") (name "/LVDS2_5_N") (class "Default")
      (node (ref "J42") (pin "18") (pinfunction "18_18") (pintype "bidirectional"))
      (node (ref "J44") (pin "L58") (pinfunction "58_L58") (pintype "bidirectional"))
    )
    (net (code "64") (name "/LVDS2_5_P") (class "Default")
      (node (ref "J42") (pin "17") (pinfunction "17_17") (pintype "bidirectional"))
      (node (ref "J44") (pin "L24") (pinfunction "24_L24") (pintype "bidirectional"))
    )
    (net (code "65") (name "/LVDS2_6_N") (class "Default")
      (node (ref "J42") (pin "21") (pinfunction "21_21") (pintype "bidirectional"))
      (node (ref "J44") (pin "L59") (pinfunction "59_L59") (pintype "bidirectional"))
    )
    (net (code "66") (name "/LVDS2_6_P") (class "Default")
      (node (ref "J42") (pin "20") (pinfunction "20_20") (pintype "bidirectional"))
      (node (ref "J44") (pin "L25") (pinfunction "25_L25") (pintype "bidirectional"))
    )
    (net (code "67") (name "/LVDS2_7_N") (class "Default")
      (node (ref "J42") (pin "24") (pinfunction "24_24") (pintype "bidirectional"))
      (node (ref "J44") (pin "L60") (pinfunction "60_L60") (pintype "bidirectional"))
    )
    (net (code "68") (name "/LVDS2_7_P") (class "Default")
      (node (ref "J42") (pin "23") (pinfunction "23_23") (pintype "bidirectional"))
      (node (ref "J44") (pin "L26") (pinfunction "26_L26") (pintype "bidirectional"))
    )
    (net (code "69") (name "/LVDS3_0_N") (class "Default")
      (node (ref "J43") (pin "3") (pinfunction "3_3") (pintype "bidirectional"))
      (node (ref "J44") (pin "L55") (pinfunction "55_L55") (pintype "bidirectional"))
    )
    (net (code "70") (name "/LVDS3_0_P") (class "Default")
      (node (ref "J43") (pin "2") (pinfunction "2_2") (pintype "bidirectional"))
      (node (ref "J44") (pin "L21") (pinfunction "21_L21") (pintype "bidirectional"))
    )
    (net (code "71") (name "/LVDS3_1_N") (class "Default")
      (node (ref "J43") (pin "6") (pinfunction "6_6") (pintype "bidirectional"))
      (node (ref "J44") (pin "L62") (pinfunction "62_L62") (pintype "bidirectional"))
    )
    (net (code "72") (name "/LVDS3_1_P") (class "Default")
      (node (ref "J43") (pin "5") (pinfunction "5_5") (pintype "bidirectional"))
      (node (ref "J44") (pin "L28") (pinfunction "28_L28") (pintype "bidirectional"))
    )
    (net (code "73") (name "/LVDS3_2_N") (class "Default")
      (node (ref "J43") (pin "9") (pinfunction "9_9") (pintype "bidirectional"))
      (node (ref "J44") (pin "L63") (pinfunction "63_L63") (pintype "bidirectional"))
    )
    (net (code "74") (name "/LVDS3_2_P") (class "Default")
      (node (ref "J43") (pin "8") (pinfunction "8_8") (pintype "bidirectional"))
      (node (ref "J44") (pin "L29") (pinfunction "29_L29") (pintype "bidirectional"))
    )
    (net (code "75") (name "/LVDS3_3_N") (class "Default")
      (node (ref "J43") (pin "12") (pinfunction "12_12") (pintype "bidirectional"))
      (node (ref "J44") (pin "L64") (pinfunction "64_L64") (pintype "bidirectional"))
    )
    (net (code "76") (name "/LVDS3_3_P") (class "Default")
      (node (ref "J43") (pin "11") (pinfunction "11_11") (pintype "bidirectional"))
      (node (ref "J44") (pin "L30") (pinfunction "30_L30") (pintype "bidirectional"))
    )
    (net (code "77") (name "/LVDS3_4_N") (class "Default")
      (node (ref "J43") (pin "15") (pinfunction "15_15") (pintype "bidirectional"))
      (node (ref "J44") (pin "L65") (pinfunction "65_L65") (pintype "bidirectional"))
    )
    (net (code "78") (name "/LVDS3_4_P") (class "Default")
      (node (ref "J43") (pin "14") (pinfunction "14_14") (pintype "bidirectional"))
      (node (ref "J44") (pin "L31") (pinfunction "31_L31") (pintype "bidirectional"))
    )
    (net (code "79") (name "/LVDS3_5_N") (class "Default")
      (node (ref "J43") (pin "18") (pinfunction "18_18") (pintype "bidirectional"))
      (node (ref "J44") (pin "L66") (pinfunction "66_L66") (pintype "bidirectional"))
    )
    (net (code "80") (name "/LVDS3_5_P") (class "Default")
      (node (ref "J43") (pin "17") (pinfunction "17_17") (pintype "bidirectional"))
      (node (ref "J44") (pin "L32") (pinfunction "32_L32") (pintype "bidirectional"))
    )
    (net (code "81") (name "/LVDS3_6_N") (class "Default")
      (node (ref "J43") (pin "21") (pinfunction "21_21") (pintype "bidirectional"))
      (node (ref "J44") (pin "L67") (pinfunction "67_L67") (pintype "bidirectional"))
    )
    (net (code "82") (name "/LVDS3_6_P") (class "Default")
      (node (ref "J43") (pin "20") (pinfunction "20_20") (pintype "bidirectional"))
      (node (ref "J44") (pin "L33") (pinfunction "33_L33") (pintype "bidirectional"))
    )
    (net (code "83") (name "/LVDS3_7_N") (class "Default")
      (node (ref "J43") (pin "24") (pinfunction "24_24") (pintype "bidirectional"))
      (node (ref "J44") (pin "L68") (pinfunction "68_L68") (pintype "bidirectional"))
    )
    (net (code "84") (name "/LVDS3_7_P") (class "Default")
      (node (ref "J43") (pin "23") (pinfunction "23_23") (pintype "bidirectional"))
      (node (ref "J44") (pin "L34") (pinfunction "34_L34") (pintype "bidirectional"))
    )
    (net (code "85") (name "/LVDS4_0_N") (class "Default")
      (node (ref "J44") (pin "U35") (pinfunction "35_U35") (pintype "bidirectional"))
      (node (ref "J45") (pin "3") (pinfunction "3_3") (pintype "bidirectional"))
    )
    (net (code "86") (name "/LVDS4_0_P") (class "Default")
      (node (ref "J44") (pin "U1") (pinfunction "1_U1") (pintype "bidirectional"))
      (node (ref "J45") (pin "2") (pinfunction "2_2") (pintype "bidirectional"))
    )
    (net (code "87") (name "/LVDS4_1_N") (class "Default")
      (node (ref "J44") (pin "U43") (pinfunction "43_U43") (pintype "bidirectional"))
      (node (ref "J45") (pin "6") (pinfunction "6_6") (pintype "bidirectional"))
    )
    (net (code "88") (name "/LVDS4_1_P") (class "Default")
      (node (ref "J44") (pin "U9") (pinfunction "9_U9") (pintype "bidirectional"))
      (node (ref "J45") (pin "5") (pinfunction "5_5") (pintype "bidirectional"))
    )
    (net (code "89") (name "/LVDS4_2_N") (class "Default")
      (node (ref "J44") (pin "U37") (pinfunction "37_U37") (pintype "bidirectional"))
      (node (ref "J45") (pin "9") (pinfunction "9_9") (pintype "bidirectional"))
    )
    (net (code "90") (name "/LVDS4_2_P") (class "Default")
      (node (ref "J44") (pin "U3") (pinfunction "3_U3") (pintype "bidirectional"))
      (node (ref "J45") (pin "8") (pinfunction "8_8") (pintype "bidirectional"))
    )
    (net (code "91") (name "/LVDS4_3_N") (class "Default")
      (node (ref "J44") (pin "U38") (pinfunction "38_U38") (pintype "bidirectional"))
      (node (ref "J45") (pin "12") (pinfunction "12_12") (pintype "bidirectional"))
    )
    (net (code "92") (name "/LVDS4_3_P") (class "Default")
      (node (ref "J44") (pin "U4") (pinfunction "4_U4") (pintype "bidirectional"))
      (node (ref "J45") (pin "11") (pinfunction "11_11") (pintype "bidirectional"))
    )
    (net (code "93") (name "/LVDS4_4_N") (class "Default")
      (node (ref "J44") (pin "U39") (pinfunction "39_U39") (pintype "bidirectional"))
      (node (ref "J45") (pin "15") (pinfunction "15_15") (pintype "bidirectional"))
    )
    (net (code "94") (name "/LVDS4_4_P") (class "Default")
      (node (ref "J44") (pin "U5") (pinfunction "5_U5") (pintype "bidirectional"))
      (node (ref "J45") (pin "14") (pinfunction "14_14") (pintype "bidirectional"))
    )
    (net (code "95") (name "/LVDS4_5_N") (class "Default")
      (node (ref "J44") (pin "U40") (pinfunction "40_U40") (pintype "bidirectional"))
      (node (ref "J45") (pin "18") (pinfunction "18_18") (pintype "bidirectional"))
    )
    (net (code "96") (name "/LVDS4_5_P") (class "Default")
      (node (ref "J44") (pin "U6") (pinfunction "6_U6") (pintype "bidirectional"))
      (node (ref "J45") (pin "17") (pinfunction "17_17") (pintype "bidirectional"))
    )
    (net (code "97") (name "/LVDS4_6_N") (class "Default")
      (node (ref "J44") (pin "U41") (pinfunction "41_U41") (pintype "bidirectional"))
      (node (ref "J45") (pin "21") (pinfunction "21_21") (pintype "bidirectional"))
    )
    (net (code "98") (name "/LVDS4_6_P") (class "Default")
      (node (ref "J44") (pin "U7") (pinfunction "7_U7") (pintype "bidirectional"))
      (node (ref "J45") (pin "20") (pinfunction "20_20") (pintype "bidirectional"))
    )
    (net (code "99") (name "/LVDS4_7_N") (class "Default")
      (node (ref "J44") (pin "U42") (pinfunction "42_U42") (pintype "bidirectional"))
      (node (ref "J45") (pin "24") (pinfunction "24_24") (pintype "bidirectional"))
    )
    (net (code "100") (name "/LVDS4_7_P") (class "Default")
      (node (ref "J44") (pin "U8") (pinfunction "8_U8") (pintype "bidirectional"))
      (node (ref "J45") (pin "23") (pinfunction "23_23") (pintype "bidirectional"))
    )
    (net (code "101") (name "/LVDS5_0_N") (class "Default")
      (node (ref "J44") (pin "U36") (pinfunction "36_U36") (pintype "bidirectional"))
      (node (ref "J46") (pin "3") (pinfunction "3_3") (pintype "bidirectional"))
    )
    (net (code "102") (name "/LVDS5_0_P") (class "Default")
      (node (ref "J44") (pin "U2") (pinfunction "2_U2") (pintype "bidirectional"))
      (node (ref "J46") (pin "2") (pinfunction "2_2") (pintype "bidirectional"))
    )
    (net (code "103") (name "/LVDS5_1_N") (class "Default")
      (node (ref "J44") (pin "U44") (pinfunction "44_U44") (pintype "bidirectional"))
      (node (ref "J46") (pin "6") (pinfunction "6_6") (pintype "bidirectional"))
    )
    (net (code "104") (name "/LVDS5_1_P") (class "Default")
      (node (ref "J44") (pin "U10") (pinfunction "10_U10") (pintype "bidirectional"))
      (node (ref "J46") (pin "5") (pinfunction "5_5") (pintype "bidirectional"))
    )
    (net (code "105") (name "/LVDS5_2_N") (class "Default")
      (node (ref "J44") (pin "U45") (pinfunction "45_U45") (pintype "bidirectional"))
      (node (ref "J46") (pin "9") (pinfunction "9_9") (pintype "bidirectional"))
    )
    (net (code "106") (name "/LVDS5_2_P") (class "Default")
      (node (ref "J44") (pin "U11") (pinfunction "11_U11") (pintype "bidirectional"))
      (node (ref "J46") (pin "8") (pinfunction "8_8") (pintype "bidirectional"))
    )
    (net (code "107") (name "/LVDS5_3_N") (class "Default")
      (node (ref "J44") (pin "U46") (pinfunction "46_U46") (pintype "bidirectional"))
      (node (ref "J46") (pin "12") (pinfunction "12_12") (pintype "bidirectional"))
    )
    (net (code "108") (name "/LVDS5_3_P") (class "Default")
      (node (ref "J44") (pin "U12") (pinfunction "12_U12") (pintype "bidirectional"))
      (node (ref "J46") (pin "11") (pinfunction "11_11") (pintype "bidirectional"))
    )
    (net (code "109") (name "/LVDS5_4_N") (class "Default")
      (node (ref "J44") (pin "U47") (pinfunction "47_U47") (pintype "bidirectional"))
      (node (ref "J46") (pin "15") (pinfunction "15_15") (pintype "bidirectional"))
    )
    (net (code "110") (name "/LVDS5_4_P") (class "Default")
      (node (ref "J44") (pin "U13") (pinfunction "13_U13") (pintype "bidirectional"))
      (node (ref "J46") (pin "14") (pinfunction "14_14") (pintype "bidirectional"))
    )
    (net (code "111") (name "/LVDS5_5_N") (class "Default")
      (node (ref "J44") (pin "U48") (pinfunction "48_U48") (pintype "bidirectional"))
      (node (ref "J46") (pin "18") (pinfunction "18_18") (pintype "bidirectional"))
    )
    (net (code "112") (name "/LVDS5_5_P") (class "Default")
      (node (ref "J44") (pin "U14") (pinfunction "14_U14") (pintype "bidirectional"))
      (node (ref "J46") (pin "17") (pinfunction "17_17") (pintype "bidirectional"))
    )
    (net (code "113") (name "/LVDS5_6_N") (class "Default")
      (node (ref "J44") (pin "U49") (pinfunction "49_U49") (pintype "bidirectional"))
      (node (ref "J46") (pin "21") (pinfunction "21_21") (pintype "bidirectional"))
    )
    (net (code "114") (name "/LVDS5_6_P") (class "Default")
      (node (ref "J44") (pin "U15") (pinfunction "15_U15") (pintype "bidirectional"))
      (node (ref "J46") (pin "20") (pinfunction "20_20") (pintype "bidirectional"))
    )
    (net (code "115") (name "/LVDS5_7_N") (class "Default")
      (node (ref "J44") (pin "U50") (pinfunction "50_U50") (pintype "bidirectional"))
      (node (ref "J46") (pin "24") (pinfunction "24_24") (pintype "bidirectional"))
    )
    (net (code "116") (name "/LVDS5_7_P") (class "Default")
      (node (ref "J44") (pin "U16") (pinfunction "16_U16") (pintype "bidirectional"))
      (node (ref "J46") (pin "23") (pinfunction "23_23") (pintype "bidirectional"))
    )
    (net (code "117") (name "/LVDS6_0_N") (class "Default")
      (node (ref "J44") (pin "U54") (pinfunction "54_U54") (pintype "bidirectional"))
      (node (ref "J47") (pin "3") (pinfunction "3_3") (pintype "bidirectional"))
    )
    (net (code "118") (name "/LVDS6_0_P") (class "Default")
      (node (ref "J44") (pin "U20") (pinfunction "20_U20") (pintype "bidirectional"))
      (node (ref "J47") (pin "2") (pinfunction "2_2") (pintype "bidirectional"))
    )
    (net (code "119") (name "/LVDS6_1_N") (class "Default")
      (node (ref "J44") (pin "U53") (pinfunction "53_U53") (pintype "bidirectional"))
      (node (ref "J47") (pin "6") (pinfunction "6_6") (pintype "bidirectional"))
    )
    (net (code "120") (name "/LVDS6_1_P") (class "Default")
      (node (ref "J44") (pin "U19") (pinfunction "19_U19") (pintype "bidirectional"))
      (node (ref "J47") (pin "5") (pinfunction "5_5") (pintype "bidirectional"))
    )
    (net (code "121") (name "/LVDS6_2_N") (class "Default")
      (node (ref "J44") (pin "U61") (pinfunction "61_U61") (pintype "bidirectional"))
      (node (ref "J47") (pin "9") (pinfunction "9_9") (pintype "bidirectional"))
    )
    (net (code "122") (name "/LVDS6_2_P") (class "Default")
      (node (ref "J44") (pin "U27") (pinfunction "27_U27") (pintype "bidirectional"))
      (node (ref "J47") (pin "8") (pinfunction "8_8") (pintype "bidirectional"))
    )
    (net (code "123") (name "/LVDS6_3_N") (class "Default")
      (node (ref "J44") (pin "U56") (pinfunction "56_U56") (pintype "bidirectional"))
      (node (ref "J47") (pin "12") (pinfunction "12_12") (pintype "bidirectional"))
    )
    (net (code "124") (name "/LVDS6_3_P") (class "Default")
      (node (ref "J44") (pin "U22") (pinfunction "22_U22") (pintype "bidirectional"))
      (node (ref "J47") (pin "11") (pinfunction "11_11") (pintype "bidirectional"))
    )
    (net (code "125") (name "/LVDS6_4_N") (class "Default")
      (node (ref "J44") (pin "U57") (pinfunction "57_U57") (pintype "bidirectional"))
      (node (ref "J47") (pin "15") (pinfunction "15_15") (pintype "bidirectional"))
    )
    (net (code "126") (name "/LVDS6_4_P") (class "Default")
      (node (ref "J44") (pin "U23") (pinfunction "23_U23") (pintype "bidirectional"))
      (node (ref "J47") (pin "14") (pinfunction "14_14") (pintype "bidirectional"))
    )
    (net (code "127") (name "/LVDS6_5_N") (class "Default")
      (node (ref "J44") (pin "U58") (pinfunction "58_U58") (pintype "bidirectional"))
      (node (ref "J47") (pin "18") (pinfunction "18_18") (pintype "bidirectional"))
    )
    (net (code "128") (name "/LVDS6_5_P") (class "Default")
      (node (ref "J44") (pin "U24") (pinfunction "24_U24") (pintype "bidirectional"))
      (node (ref "J47") (pin "17") (pinfunction "17_17") (pintype "bidirectional"))
    )
    (net (code "129") (name "/LVDS6_6_N") (class "Default")
      (node (ref "J44") (pin "U59") (pinfunction "59_U59") (pintype "bidirectional"))
      (node (ref "J47") (pin "21") (pinfunction "21_21") (pintype "bidirectional"))
    )
    (net (code "130") (name "/LVDS6_6_P") (class "Default")
      (node (ref "J44") (pin "U25") (pinfunction "25_U25") (pintype "bidirectional"))
      (node (ref "J47") (pin "20") (pinfunction "20_20") (pintype "bidirectional"))
    )
    (net (code "131") (name "/LVDS6_7_N") (class "Default")
      (node (ref "J44") (pin "U60") (pinfunction "60_U60") (pintype "bidirectional"))
      (node (ref "J47") (pin "24") (pinfunction "24_24") (pintype "bidirectional"))
    )
    (net (code "132") (name "/LVDS6_7_P") (class "Default")
      (node (ref "J44") (pin "U26") (pinfunction "26_U26") (pintype "bidirectional"))
      (node (ref "J47") (pin "23") (pinfunction "23_23") (pintype "bidirectional"))
    )
    (net (code "133") (name "/LVDS7_0_N") (class "Default")
      (node (ref "J44") (pin "U55") (pinfunction "55_U55") (pintype "bidirectional"))
      (node (ref "J48") (pin "3") (pinfunction "3_3") (pintype "bidirectional"))
    )
    (net (code "134") (name "/LVDS7_0_P") (class "Default")
      (node (ref "J44") (pin "U21") (pinfunction "21_U21") (pintype "bidirectional"))
      (node (ref "J48") (pin "2") (pinfunction "2_2") (pintype "bidirectional"))
    )
    (net (code "135") (name "/LVDS7_1_N") (class "Default")
      (node (ref "J44") (pin "U62") (pinfunction "62_U62") (pintype "bidirectional"))
      (node (ref "J48") (pin "6") (pinfunction "6_6") (pintype "bidirectional"))
    )
    (net (code "136") (name "/LVDS7_1_P") (class "Default")
      (node (ref "J44") (pin "U28") (pinfunction "28_U28") (pintype "bidirectional"))
      (node (ref "J48") (pin "5") (pinfunction "5_5") (pintype "bidirectional"))
    )
    (net (code "137") (name "/LVDS7_2_N") (class "Default")
      (node (ref "J44") (pin "U63") (pinfunction "63_U63") (pintype "bidirectional"))
      (node (ref "J48") (pin "9") (pinfunction "9_9") (pintype "bidirectional"))
    )
    (net (code "138") (name "/LVDS7_2_P") (class "Default")
      (node (ref "J44") (pin "U29") (pinfunction "29_U29") (pintype "bidirectional"))
      (node (ref "J48") (pin "8") (pinfunction "8_8") (pintype "bidirectional"))
    )
    (net (code "139") (name "/LVDS7_3_N") (class "Default")
      (node (ref "J44") (pin "U64") (pinfunction "64_U64") (pintype "bidirectional"))
      (node (ref "J48") (pin "12") (pinfunction "12_12") (pintype "bidirectional"))
    )
    (net (code "140") (name "/LVDS7_3_P") (class "Default")
      (node (ref "J44") (pin "U30") (pinfunction "30_U30") (pintype "bidirectional"))
      (node (ref "J48") (pin "11") (pinfunction "11_11") (pintype "bidirectional"))
    )
    (net (code "141") (name "/LVDS7_4_N") (class "Default")
      (node (ref "J44") (pin "U65") (pinfunction "65_U65") (pintype "bidirectional"))
      (node (ref "J48") (pin "15") (pinfunction "15_15") (pintype "bidirectional"))
    )
    (net (code "142") (name "/LVDS7_4_P") (class "Default")
      (node (ref "J44") (pin "U31") (pinfunction "31_U31") (pintype "bidirectional"))
      (node (ref "J48") (pin "14") (pinfunction "14_14") (pintype "bidirectional"))
    )
    (net (code "143") (name "/LVDS7_5_N") (class "Default")
      (node (ref "J44") (pin "U66") (pinfunction "66_U66") (pintype "bidirectional"))
      (node (ref "J48") (pin "18") (pinfunction "18_18") (pintype "bidirectional"))
    )
    (net (code "144") (name "/LVDS7_5_P") (class "Default")
      (node (ref "J44") (pin "U32") (pinfunction "32_U32") (pintype "bidirectional"))
      (node (ref "J48") (pin "17") (pinfunction "17_17") (pintype "bidirectional"))
    )
    (net (code "145") (name "/LVDS7_6_N") (class "Default")
      (node (ref "J44") (pin "U67") (pinfunction "67_U67") (pintype "bidirectional"))
      (node (ref "J48") (pin "21") (pinfunction "21_21") (pintype "bidirectional"))
    )
    (net (code "146") (name "/LVDS7_6_P") (class "Default")
      (node (ref "J44") (pin "U33") (pinfunction "33_U33") (pintype "bidirectional"))
      (node (ref "J48") (pin "20") (pinfunction "20_20") (pintype "bidirectional"))
    )
    (net (code "147") (name "/LVDS7_7_N") (class "Default")
      (node (ref "J44") (pin "U68") (pinfunction "68_U68") (pintype "bidirectional"))
      (node (ref "J48") (pin "24") (pinfunction "24_24") (pintype "bidirectional"))
    )
    (net (code "148") (name "/LVDS7_7_P") (class "Default")
      (node (ref "J44") (pin "U34") (pinfunction "34_U34") (pintype "bidirectional"))
      (node (ref "J48") (pin "23") (pinfunction "23_23") (pintype "bidirectional"))
    )
    (net (code "149") (name "/VHDCI0_SCL") (class "Default")
      (node (ref "B13") (pin "1") (pinfunction "1_1") (pintype "bidirectional"))
      (node (ref "IC1") (pin "11") (pinfunction "Y_11") (pintype "bidirectional"))
      (node (ref "IC1") (pin "4") (pinfunction "Y_4") (pintype "bidirectional"))
      (node (ref "IC33") (pin "19") (pinfunction "SCL_19") (pintype "bidirectional"))
      (node (ref "J44") (pin "L17") (pinfunction "17_L17") (pintype "bidirectional"))
    )
    (net (code "150") (name "/VHDCI0_SDA") (class "Default")
      (node (ref "B14") (pin "1") (pinfunction "1_1") (pintype "bidirectional"))
      (node (ref "IC1") (pin "1") (pinfunction "Y_1") (pintype "bidirectional"))
      (node (ref "IC1") (pin "8") (pinfunction "Y_8") (pintype "bidirectional"))
      (node (ref "IC33") (pin "20") (pinfunction "SDA_20") (pintype "bidirectional"))
      (node (ref "J44") (pin "L51") (pinfunction "51_L51") (pintype "bidirectional"))
    )
    (net (code "151") (name "/VHDCI1_SCL") (class "Default")
      (node (ref "B15") (pin "1") (pinfunction "1_1") (pintype "bidirectional"))
      (node (ref "IC2") (pin "11") (pinfunction "Y_11") (pintype "bidirectional"))
      (node (ref "IC2") (pin "4") (pinfunction "Y_4") (pintype "bidirectional"))
      (node (ref "IC35") (pin "19") (pinfunction "SCL_19") (pintype "bidirectional"))
      (node (ref "J44") (pin "U17") (pinfunction "17_U17") (pintype "bidirectional"))
    )
    (net (code "152") (name "/VHDCI1_SDA") (class "Default")
      (node (ref "B16") (pin "1") (pinfunction "1_1") (pintype "bidirectional"))
      (node (ref "IC2") (pin "1") (pinfunction "Y_1") (pintype "bidirectional"))
      (node (ref "IC2") (pin "8") (pinfunction "Y_8") (pintype "bidirectional"))
      (node (ref "IC35") (pin "20") (pinfunction "SDA_20") (pintype "bidirectional"))
      (node (ref "J44") (pin "U51") (pinfunction "51_U51") (pintype "bidirectional"))
    )
    (net (code "153") (name "GND") (class "Default")
      (node (ref "B5") (pin "1") (pinfunction "1_1") (pintype "bidirectional"))
      (node (ref "B6") (pin "1") (pinfunction "1_1") (pintype "bidirectional"))
      (node (ref "B8") (pin "1") (pinfunction "1_1") (pintype "bidirectional"))
      (node (ref "C1") (pin "2") (pinfunction "2_2") (pintype "passive"))
      (node (ref "C2") (pin "2") (pinfunction "2_2") (pintype "passive"))
      (node (ref "C76") (pin "1") (pinfunction "1_1") (pintype "passive"))
      (node (ref "C77") (pin "1") (pinfunction "1_1") (pintype "passive"))
      (node (ref "C78") (pin "1") (pinfunction "1_1") (pintype "passive"))
      (node (ref "C79") (pin "1") (pinfunction "1_1") (pintype "passive"))
      (node (ref "C80") (pin "1") (pinfunction "1_1") (pintype "passive"))
      (node (ref "C81") (pin "2") (pinfunction "2_2") (pintype "passive"))
      (node (ref "C82") (pin "1") (pinfunction "1_1") (pintype "passive"))
      (node (ref "C83") (pin "1") (pinfunction "1_1") (pintype "passive"))
      (node (ref "C84") (pin "1") (pinfunction "1_1") (pintype "passive"))
      (node (ref "C85") (pin "1") (pinfunction "1_1") (pintype "passive"))
      (node (ref "C86") (pin "1") (pinfunction "1_1") (pintype "passive"))
      (node (ref "C87") (pin "2") (pinfunction "2_2") (pintype "passive"))
      (node (ref "C88") (pin "2") (pinfunction "2_2") (pintype "passive"))
      (node (ref "FL1") (pin "4") (pinfunction "CG_4") (pintype "passive"))
      (node (ref "IC1") (pin "7") (pinfunction "GND_7") (pintype "power_in"))
      (node (ref "IC2") (pin "7") (pinfunction "GND_7") (pintype "power_in"))
      (node (ref "IC33") (pin "25") (pinfunction "EP_25") (pintype "power_in"))
      (node (ref "IC33") (pin "9") (pinfunction "GND_9") (pintype "power_in"))
      (node (ref "IC34") (pin "2") (pinfunction "VSS_2") (pintype "power_in"))
      (node (ref "IC35") (pin "25") (pinfunction "EP_25") (pintype "power_in"))
      (node (ref "IC35") (pin "9") (pinfunction "GND_9") (pintype "power_in"))
      (node (ref "IC36") (pin "2") (pinfunction "VSS_2") (pintype "power_in"))
      (node (ref "J40") (pin "1") (pinfunction "1_1") (pintype "bidirectional"))
      (node (ref "J40") (pin "10") (pinfunction "10_10") (pintype "bidirectional"))
      (node (ref "J40") (pin "13") (pinfunction "13_13") (pintype "bidirectional"))
      (node (ref "J40") (pin "16") (pinfunction "16_16") (pintype "bidirectional"))
      (node (ref "J40") (pin "19") (pinfunction "19_19") (pintype "bidirectional"))
      (node (ref "J40") (pin "22") (pinfunction "22_22") (pintype "bidirectional"))
      (node (ref "J40") (pin "25") (pinfunction "25_25") (pintype "bidirectional"))
      (node (ref "J40") (pin "4") (pinfunction "4_4") (pintype "bidirectional"))
      (node (ref "J40") (pin "7") (pinfunction "7_7") (pintype "bidirectional"))
      (node (ref "J41") (pin "1") (pinfunction "1_1") (pintype "bidirectional"))
      (node (ref "J41") (pin "10") (pinfunction "10_10") (pintype "bidirectional"))
      (node (ref "J41") (pin "13") (pinfunction "13_13") (pintype "bidirectional"))
      (node (ref "J41") (pin "16") (pinfunction "16_16") (pintype "bidirectional"))
      (node (ref "J41") (pin "19") (pinfunction "19_19") (pintype "bidirectional"))
      (node (ref "J41") (pin "22") (pinfunction "22_22") (pintype "bidirectional"))
      (node (ref "J41") (pin "25") (pinfunction "25_25") (pintype "bidirectional"))
      (node (ref "J41") (pin "4") (pinfunction "4_4") (pintype "bidirectional"))
      (node (ref "J41") (pin "7") (pinfunction "7_7") (pintype "bidirectional"))
      (node (ref "J42") (pin "1") (pinfunction "1_1") (pintype "bidirectional"))
      (node (ref "J42") (pin "10") (pinfunction "10_10") (pintype "bidirectional"))
      (node (ref "J42") (pin "13") (pinfunction "13_13") (pintype "bidirectional"))
      (node (ref "J42") (pin "16") (pinfunction "16_16") (pintype "bidirectional"))
      (node (ref "J42") (pin "19") (pinfunction "19_19") (pintype "bidirectional"))
      (node (ref "J42") (pin "22") (pinfunction "22_22") (pintype "bidirectional"))
      (node (ref "J42") (pin "25") (pinfunction "25_25") (pintype "bidirectional"))
      (node (ref "J42") (pin "4") (pinfunction "4_4") (pintype "bidirectional"))
      (node (ref "J42") (pin "7") (pinfunction "7_7") (pintype "bidirectional"))
      (node (ref "J43") (pin "1") (pinfunction "1_1") (pintype "bidirectional"))
      (node (ref "J43") (pin "10") (pinfunction "10_10") (pintype "bidirectional"))
      (node (ref "J43") (pin "13") (pinfunction "13_13") (pintype "bidirectional"))
      (node (ref "J43") (pin "16") (pinfunction "16_16") (pintype "bidirectional"))
      (node (ref "J43") (pin "19") (pinfunction "19_19") (pintype "bidirectional"))
      (node (ref "J43") (pin "22") (pinfunction "22_22") (pintype "bidirectional"))
      (node (ref "J43") (pin "25") (pinfunction "25_25") (pintype "bidirectional"))
      (node (ref "J43") (pin "4") (pinfunction "4_4") (pintype "bidirectional"))
      (node (ref "J43") (pin "7") (pinfunction "7_7") (pintype "bidirectional"))
      (node (ref "J44") (pin "69") (pinfunction "69_69") (pintype "passive"))
      (node (ref "J44") (pin "70") (pinfunction "70_70") (pintype "passive"))
      (node (ref "J44") (pin "71") (pinfunction "71_71") (pintype "passive"))
      (node (ref "J44") (pin "72") (pinfunction "72_72") (pintype "passive"))
      (node (ref "J44") (pin "L18") (pinfunction "18_L18") (pintype "bidirectional"))
      (node (ref "J44") (pin "U18") (pinfunction "18_U18") (pintype "bidirectional"))
      (node (ref "J45") (pin "1") (pinfunction "1_1") (pintype "bidirectional"))
      (node (ref "J45") (pin "10") (pinfunction "10_10") (pintype "bidirectional"))
      (node (ref "J45") (pin "13") (pinfunction "13_13") (pintype "bidirectional"))
      (node (ref "J45") (pin "16") (pinfunction "16_16") (pintype "bidirectional"))
      (node (ref "J45") (pin "19") (pinfunction "19_19") (pintype "bidirectional"))
      (node (ref "J45") (pin "22") (pinfunction "22_22") (pintype "bidirectional"))
      (node (ref "J45") (pin "25") (pinfunction "25_25") (pintype "bidirectional"))
      (node (ref "J45") (pin "4") (pinfunction "4_4") (pintype "bidirectional"))
      (node (ref "J45") (pin "7") (pinfunction "7_7") (pintype "bidirectional"))
      (node (ref "J46") (pin "1") (pinfunction "1_1") (pintype "bidirectional"))
      (node (ref "J46") (pin "10") (pinfunction "10_10") (pintype "bidirectional"))
      (node (ref "J46") (pin "13") (pinfunction "13_13") (pintype "bidirectional"))
      (node (ref "J46") (pin "16") (pinfunction "16_16") (pintype "bidirectional"))
      (node (ref "J46") (pin "19") (pinfunction "19_19") (pintype "bidirectional"))
      (node (ref "J46") (pin "22") (pinfunction "22_22") (pintype "bidirectional"))
      (node (ref "J46") (pin "25") (pinfunction "25_25") (pintype "bidirectional"))
      (node (ref "J46") (pin "4") (pinfunction "4_4") (pintype "bidirectional"))
      (node (ref "J46") (pin "7") (pinfunction "7_7") (pintype "bidirectional"))
      (node (ref "J47") (pin "1") (pinfunction "1_1") (pintype "bidirectional"))
      (node (ref "J47") (pin "10") (pinfunction "10_10") (pintype "bidirectional"))
      (node (ref "J47") (pin "13") (pinfunction "13_13") (pintype "bidirectional"))
      (node (ref "J47") (pin "16") (pinfunction "16_16") (pintype "bidirectional"))
      (node (ref "J47") (pin "19") (pinfunction "19_19") (pintype "bidirectional"))
      (node (ref "J47") (pin "22") (pinfunction "22_22") (pintype "bidirectional"))
      (node (ref "J47") (pin "25") (pinfunction "25_25") (pintype "bidirectional"))
      (node (ref "J47") (pin "4") (pinfunction "4_4") (pintype "bidirectional"))
      (node (ref "J47") (pin "7") (pinfunction "7_7") (pintype "bidirectional"))
      (node (ref "J48") (pin "1") (pinfunction "1_1") (pintype "bidirectional"))
      (node (ref "J48") (pin "10") (pinfunction "10_10") (pintype "bidirectional"))
      (node (ref "J48") (pin "13") (pinfunction "13_13") (pintype "bidirectional"))
      (node (ref "J48") (pin "16") (pinfunction "16_16") (pintype "bidirectional"))
      (node (ref "J48") (pin "19") (pinfunction "19_19") (pintype "bidirectional"))
      (node (ref "J48") (pin "22") (pinfunction "22_22") (pintype "bidirectional"))
      (node (ref "J48") (pin "25") (pinfunction "25_25") (pintype "bidirectional"))
      (node (ref "J48") (pin "4") (pinfunction "4_4") (pintype "bidirectional"))
      (node (ref "J48") (pin "7") (pinfunction "7_7") (pintype "bidirectional"))
      (node (ref "LD1") (pin "1") (pinfunction "C_1") (pintype "passive"))
      (node (ref "LD2") (pin "1") (pinfunction "C_1") (pintype "passive"))
      (node (ref "LD3") (pin "1") (pinfunction "C_1") (pintype "passive"))
      (node (ref "R178") (pin "1") (pinfunction "1_1") (pintype "passive"))
      (node (ref "R179") (pin "1") (pinfunction "1_1") (pintype "passive"))
      (node (ref "R181") (pin "1") (pinfunction "1_1") (pintype "passive"))
      (node (ref "R192") (pin "1") (pinfunction "1_1") (pintype "passive"))
      (node (ref "R193") (pin "1") (pinfunction "1_1") (pintype "passive"))
      (node (ref "R195") (pin "1") (pinfunction "1_1") (pintype "passive"))
      (node (ref "R4") (pin "1") (pinfunction "1_1") (pintype "passive"))
      (node (ref "R5") (pin "1") (pinfunction "1_1") (pintype "passive"))
      (node (ref "SW1") (pin "3") (pinfunction "3_3") (pintype "bidirectional"))
      (node (ref "SW1") (pin "4") (pinfunction "4_4") (pintype "bidirectional"))
      (node (ref "T1") (pin "2") (pinfunction "S_2") (pintype "passive"))
      (node (ref "T2") (pin "2") (pinfunction "S_2") (pintype "passive"))
    )
    (net (code "154") (name "GNDF") (class "Default")
      (node (ref "FL1") (pin "3") (pinfunction "PSG_3") (pintype "passive"))
      (node (ref "J1") (pin "1") (pinfunction "1_1") (pintype "bidirectional"))
      (node (ref "J2") (pin "1") (pinfunction "1_1") (pintype "bidirectional"))
      (node (ref "J49") (pin "a11") (pinfunction "a11_a11") (pintype "bidirectional"))
      (node (ref "J49") (pin "a18") (pinfunction "a18_a18") (pintype "bidirectional"))
      (node (ref "J49") (pin "a25") (pinfunction "a25_a25") (pintype "bidirectional"))
      (node (ref "J49") (pin "a32") (pinfunction "a32_a32") (pintype "bidirectional"))
      (node (ref "J49") (pin "a4") (pinfunction "a4_a4") (pintype "bidirectional"))
      (node (ref "J49") (pin "b11") (pinfunction "b11_b11") (pintype "bidirectional"))
      (node (ref "J49") (pin "b18") (pinfunction "b18_b18") (pintype "bidirectional"))
      (node (ref "J49") (pin "b25") (pinfunction "b25_b25") (pintype "bidirectional"))
      (node (ref "J49") (pin "b32") (pinfunction "b32_b32") (pintype "bidirectional"))
      (node (ref "J49") (pin "b4") (pinfunction "b4_b4") (pintype "bidirectional"))
      (node (ref "J49") (pin "c11") (pinfunction "c11_c11") (pintype "bidirectional"))
      (node (ref "J49") (pin "c18") (pinfunction "c18_c18") (pintype "bidirectional"))
      (node (ref "J49") (pin "c25") (pinfunction "c25_c25") (pintype "bidirectional"))
      (node (ref "J49") (pin "c32") (pinfunction "c32_c32") (pintype "bidirectional"))
      (node (ref "J49") (pin "c4") (pinfunction "c4_c4") (pintype "bidirectional"))
    )
    (net (code "155") (name "Net-(B11-Pad1)") (class "Default")
      (node (ref "B11") (pin "1") (pinfunction "1_1") (pintype "bidirectional"))
      (node (ref "C1") (pin "1") (pinfunction "1_1") (pintype "passive"))
      (node (ref "R4") (pin "2") (pinfunction "2_2") (pintype "passive"))
    )
    (net (code "156") (name "Net-(B12-Pad1)") (class "Default")
      (node (ref "B12") (pin "1") (pinfunction "1_1") (pintype "bidirectional"))
      (node (ref "C2") (pin "1") (pinfunction "1_1") (pintype "passive"))
      (node (ref "R5") (pin "2") (pinfunction "2_2") (pintype "passive"))
    )
    (net (code "157") (name "Net-(IC1A-E)") (class "Default")
      (node (ref "IC1") (pin "12") (pinfunction "E_12") (pintype "input"))
      (node (ref "IC1") (pin "13") (pinfunction "E_13") (pintype "input"))
      (node (ref "IC1") (pin "5") (pinfunction "E_5") (pintype "input"))
      (node (ref "IC1") (pin "6") (pinfunction "E_6") (pintype "input"))
      (node (ref "R7") (pin "1") (pinfunction "1_1") (pintype "passive"))
      (node (ref "T1") (pin "3") (pinfunction "D_3") (pintype "passive"))
    )
    (net (code "158") (name "Net-(IC2A-E)") (class "Default")
      (node (ref "IC2") (pin "12") (pinfunction "E_12") (pintype "input"))
      (node (ref "IC2") (pin "13") (pinfunction "E_13") (pintype "input"))
      (node (ref "IC2") (pin "5") (pinfunction "E_5") (pintype "input"))
      (node (ref "IC2") (pin "6") (pinfunction "E_6") (pintype "input"))
      (node (ref "R9") (pin "1") (pinfunction "1_1") (pintype "passive"))
      (node (ref "T2") (pin "3") (pinfunction "D_3") (pintype "passive"))
    )
    (net (code "159") (name "Net-(IC33-A0)") (class "Default")
      (node (ref "IC33") (pin "22") (pinfunction "A0_22") (pintype "input"))
      (node (ref "R181") (pin "2") (pinfunction "2_2") (pintype "passive"))
    )
    (net (code "160") (name "Net-(IC33-A1)") (class "Default")
      (node (ref "IC33") (pin "23") (pinfunction "A1_23") (pintype "input"))
      (node (ref "R179") (pin "2") (pinfunction "2_2") (pintype "passive"))
    )
    (net (code "161") (name "Net-(IC33-A2)") (class "Default")
      (node (ref "IC33") (pin "18") (pinfunction "A2_18") (pintype "input"))
      (node (ref "R178") (pin "2") (pinfunction "2_2") (pintype "passive"))
    )
    (net (code "162") (name "Net-(IC33-~{RESET})") (class "Default")
      (node (ref "IC33") (pin "24") (pinfunction "~{RESET}_24") (pintype "input"))
      (node (ref "R6") (pin "2") (pinfunction "2_2") (pintype "passive"))
      (node (ref "SW1") (pin "2") (pinfunction "2_2") (pintype "bidirectional"))
      (node (ref "T1") (pin "1") (pinfunction "G_1") (pintype "passive"))
    )
    (net (code "163") (name "Net-(IC35-A0)") (class "Default")
      (node (ref "IC35") (pin "22") (pinfunction "A0_22") (pintype "input"))
      (node (ref "R195") (pin "2") (pinfunction "2_2") (pintype "passive"))
    )
    (net (code "164") (name "Net-(IC35-A1)") (class "Default")
      (node (ref "IC35") (pin "23") (pinfunction "A1_23") (pintype "input"))
      (node (ref "R193") (pin "2") (pinfunction "2_2") (pintype "passive"))
    )
    (net (code "165") (name "Net-(IC35-A2)") (class "Default")
      (node (ref "IC35") (pin "18") (pinfunction "A2_18") (pintype "input"))
      (node (ref "R192") (pin "2") (pinfunction "2_2") (pintype "passive"))
    )
    (net (code "166") (name "Net-(IC35-~{RESET})") (class "Default")
      (node (ref "IC35") (pin "24") (pinfunction "~{RESET}_24") (pintype "input"))
      (node (ref "R8") (pin "2") (pinfunction "2_2") (pintype "passive"))
      (node (ref "SW1") (pin "1") (pinfunction "1_1") (pintype "bidirectional"))
      (node (ref "T2") (pin "1") (pinfunction "G_1") (pintype "passive"))
    )
    (net (code "167") (name "Net-(LD1-A)") (class "Default")
      (node (ref "LD1") (pin "2") (pinfunction "A_2") (pintype "passive"))
      (node (ref "R1") (pin "1") (pinfunction "1_1") (pintype "passive"))
    )
    (net (code "168") (name "Net-(LD2-A)") (class "Default")
      (node (ref "LD2") (pin "2") (pinfunction "A_2") (pintype "passive"))
      (node (ref "R2") (pin "2") (pinfunction "2_2") (pintype "passive"))
    )
    (net (code "169") (name "Net-(LD3-A)") (class "Default")
      (node (ref "LD3") (pin "2") (pinfunction "A_2") (pintype "passive"))
      (node (ref "R3") (pin "2") (pinfunction "2_2") (pintype "passive"))
    )
    (net (code "170") (name "P3V3_MP0") (class "Default")
      (node (ref "B7") (pin "1") (pinfunction "1_1") (pintype "bidirectional"))
      (node (ref "B9") (pin "1") (pinfunction "1_1") (pintype "bidirectional"))
      (node (ref "C76") (pin "2") (pinfunction "2_2") (pintype "passive"))
      (node (ref "C77") (pin "2") (pinfunction "2_2") (pintype "passive"))
      (node (ref "C78") (pin "2") (pinfunction "2_2") (pintype "passive"))
      (node (ref "C79") (pin "2") (pinfunction "2_2") (pintype "passive"))
      (node (ref "C80") (pin "2") (pinfunction "2_2") (pintype "passive"))
      (node (ref "C81") (pin "1") (pinfunction "1_1") (pintype "passive"))
      (node (ref "C82") (pin "2") (pinfunction "2_2") (pintype "passive"))
      (node (ref "C83") (pin "2") (pinfunction "2_2") (pintype "passive"))
      (node (ref "C84") (pin "2") (pinfunction "2_2") (pintype "passive"))
      (node (ref "C85") (pin "2") (pinfunction "2_2") (pintype "passive"))
      (node (ref "C86") (pin "2") (pinfunction "2_2") (pintype "passive"))
      (node (ref "C87") (pin "1") (pinfunction "1_1") (pintype "passive"))
      (node (ref "IC1") (pin "14") (pinfunction "VCC_14") (pintype "power_in"))
      (node (ref "IC2") (pin "14") (pinfunction "VCC_14") (pintype "power_in"))
      (node (ref "IC33") (pin "21") (pinfunction "VCC_21") (pintype "power_in"))
      (node (ref "IC34") (pin "4") (pinfunction "VCC_4") (pintype "power_in"))
      (node (ref "IC35") (pin "21") (pinfunction "VCC_21") (pintype "power_in"))
      (node (ref "IC36") (pin "4") (pinfunction "VCC_4") (pintype "power_in"))
      (node (ref "J40") (pin "30") (pinfunction "30_30") (pintype "bidirectional"))
      (node (ref "J41") (pin "30") (pinfunction "30_30") (pintype "bidirectional"))
      (node (ref "J42") (pin "30") (pinfunction "30_30") (pintype "bidirectional"))
      (node (ref "J43") (pin "30") (pinfunction "30_30") (pintype "bidirectional"))
      (node (ref "J44") (pin "L52") (pinfunction "52_L52") (pintype "bidirectional"))
      (node (ref "J44") (pin "U52") (pinfunction "52_U52") (pintype "bidirectional"))
      (node (ref "J45") (pin "30") (pinfunction "30_30") (pintype "bidirectional"))
      (node (ref "J46") (pin "30") (pinfunction "30_30") (pintype "bidirectional"))
      (node (ref "J47") (pin "30") (pinfunction "30_30") (pintype "bidirectional"))
      (node (ref "J48") (pin "30") (pinfunction "30_30") (pintype "bidirectional"))
      (node (ref "R174") (pin "2") (pinfunction "2_2") (pintype "passive"))
      (node (ref "R175") (pin "2") (pinfunction "2_2") (pintype "passive"))
      (node (ref "R176") (pin "2") (pinfunction "2_2") (pintype "passive"))
      (node (ref "R177") (pin "2") (pinfunction "2_2") (pintype "passive"))
      (node (ref "R180") (pin "2") (pinfunction "2_2") (pintype "passive"))
      (node (ref "R182") (pin "2") (pinfunction "2_2") (pintype "passive"))
      (node (ref "R183") (pin "2") (pinfunction "2_2") (pintype "passive"))
      (node (ref "R184") (pin "2") (pinfunction "2_2") (pintype "passive"))
      (node (ref "R185") (pin "2") (pinfunction "2_2") (pintype "passive"))
      (node (ref "R186") (pin "2") (pinfunction "2_2") (pintype "passive"))
      (node (ref "R188") (pin "2") (pinfunction "2_2") (pintype "passive"))
      (node (ref "R189") (pin "2") (pinfunction "2_2") (pintype "passive"))
      (node (ref "R190") (pin "2") (pinfunction "2_2") (pintype "passive"))
      (node (ref "R191") (pin "2") (pinfunction "2_2") (pintype "passive"))
      (node (ref "R194") (pin "2") (pinfunction "2_2") (pintype "passive"))
      (node (ref "R196") (pin "2") (pinfunction "2_2") (pintype "passive"))
      (node (ref "R197") (pin "2") (pinfunction "2_2") (pintype "passive"))
      (node (ref "R198") (pin "2") (pinfunction "2_2") (pintype "passive"))
      (node (ref "R199") (pin "2") (pinfunction "2_2") (pintype "passive"))
      (node (ref "R2") (pin "1") (pinfunction "1_1") (pintype "passive"))
      (node (ref "R200") (pin "2") (pinfunction "2_2") (pintype "passive"))
      (node (ref "R3") (pin "1") (pinfunction "1_1") (pintype "passive"))
      (node (ref "R6") (pin "1") (pinfunction "1_1") (pintype "passive"))
      (node (ref "R7") (pin "2") (pinfunction "2_2") (pintype "passive"))
      (node (ref "R8") (pin "1") (pinfunction "1_1") (pintype "passive"))
      (node (ref "R9") (pin "2") (pinfunction "2_2") (pintype "passive"))
    )
    (net (code "171") (name "P12V0") (class "Default")
      (node (ref "B10") (pin "1") (pinfunction "1_1") (pintype "bidirectional"))
      (node (ref "C88") (pin "1") (pinfunction "1_1") (pintype "passive"))
      (node (ref "FL1") (pin "2") (pinfunction "CB_2") (pintype "passive"))
      (node (ref "J40") (pin "28") (pinfunction "28_28") (pintype "bidirectional"))
      (node (ref "J40") (pin "29") (pinfunction "29_29") (pintype "bidirectional"))
      (node (ref "J41") (pin "28") (pinfunction "28_28") (pintype "bidirectional"))
      (node (ref "J41") (pin "29") (pinfunction "29_29") (pintype "bidirectional"))
      (node (ref "J42") (pin "28") (pinfunction "28_28") (pintype "bidirectional"))
      (node (ref "J42") (pin "29") (pinfunction "29_29") (pintype "bidirectional"))
      (node (ref "J43") (pin "28") (pinfunction "28_28") (pintype "bidirectional"))
      (node (ref "J43") (pin "29") (pinfunction "29_29") (pintype "bidirectional"))
      (node (ref "J45") (pin "28") (pinfunction "28_28") (pintype "bidirectional"))
      (node (ref "J45") (pin "29") (pinfunction "29_29") (pintype "bidirectional"))
      (node (ref "J46") (pin "28") (pinfunction "28_28") (pintype "bidirectional"))
      (node (ref "J46") (pin "29") (pinfunction "29_29") (pintype "bidirectional"))
      (node (ref "J47") (pin "28") (pinfunction "28_28") (pintype "bidirectional"))
      (node (ref "J47") (pin "29") (pinfunction "29_29") (pintype "bidirectional"))
      (node (ref "J48") (pin "28") (pinfunction "28_28") (pintype "bidirectional"))
      (node (ref "J48") (pin "29") (pinfunction "29_29") (pintype "bidirectional"))
      (node (ref "R1") (pin "2") (pinfunction "2_2") (pintype "passive"))
    )
    (net (code "172") (name "P12V0F") (class "Default")
      (node (ref "FL1") (pin "1") (pinfunction "B_1") (pintype "passive"))
      (node (ref "J1") (pin "3") (pinfunction "3_3") (pintype "bidirectional"))
      (node (ref "J2") (pin "3") (pinfunction "3_3") (pintype "bidirectional"))
      (node (ref "J49") (pin "a1") (pinfunction "a1_a1") (pintype "bidirectional"))
      (node (ref "J49") (pin "a2") (pinfunction "a2_a2") (pintype "bidirectional"))
      (node (ref "J49") (pin "b1") (pinfunction "b1_b1") (pintype "bidirectional"))
      (node (ref "J49") (pin "b2") (pinfunction "b2_b2") (pintype "bidirectional"))
      (node (ref "J49") (pin "c1") (pinfunction "c1_c1") (pintype "bidirectional"))
      (node (ref "J49") (pin "c2") (pinfunction "c2_c2") (pintype "bidirectional"))
    )
    (net (code "173") (name "unconnected-(IC33-SC5-Pad13)") (class "Default")
      (node (ref "IC33") (pin "13") (pinfunction "SC5_13") (pintype "bidirectional"))
    )
    (net (code "174") (name "unconnected-(IC33-SC6-Pad15)") (class "Default")
      (node (ref "IC33") (pin "15") (pinfunction "SC6_15") (pintype "bidirectional"))
    )
    (net (code "175") (name "unconnected-(IC33-SC7-Pad17)") (class "Default")
      (node (ref "IC33") (pin "17") (pinfunction "SC7_17") (pintype "bidirectional"))
    )
    (net (code "176") (name "unconnected-(IC33-SD5-Pad12)") (class "Default")
      (node (ref "IC33") (pin "12") (pinfunction "SD5_12") (pintype "bidirectional"))
    )
    (net (code "177") (name "unconnected-(IC33-SD6-Pad14)") (class "Default")
      (node (ref "IC33") (pin "14") (pinfunction "SD6_14") (pintype "bidirectional"))
    )
    (net (code "178") (name "unconnected-(IC33-SD7-Pad16)") (class "Default")
      (node (ref "IC33") (pin "16") (pinfunction "SD7_16") (pintype "bidirectional"))
    )
    (net (code "179") (name "unconnected-(IC34-NC-Pad5)") (class "Default")
      (node (ref "IC34") (pin "5") (pinfunction "NC_5") (pintype "passive"))
    )
    (net (code "180") (name "unconnected-(IC35-SC5-Pad13)") (class "Default")
      (node (ref "IC35") (pin "13") (pinfunction "SC5_13") (pintype "bidirectional"))
    )
    (net (code "181") (name "unconnected-(IC35-SC6-Pad15)") (class "Default")
      (node (ref "IC35") (pin "15") (pinfunction "SC6_15") (pintype "bidirectional"))
    )
    (net (code "182") (name "unconnected-(IC35-SC7-Pad17)") (class "Default")
      (node (ref "IC35") (pin "17") (pinfunction "SC7_17") (pintype "bidirectional"))
    )
    (net (code "183") (name "unconnected-(IC35-SD5-Pad12)") (class "Default")
      (node (ref "IC35") (pin "12") (pinfunction "SD5_12") (pintype "bidirectional"))
    )
    (net (code "184") (name "unconnected-(IC35-SD6-Pad14)") (class "Default")
      (node (ref "IC35") (pin "14") (pinfunction "SD6_14") (pintype "bidirectional"))
    )
    (net (code "185") (name "unconnected-(IC35-SD7-Pad16)") (class "Default")
      (node (ref "IC35") (pin "16") (pinfunction "SD7_16") (pintype "bidirectional"))
    )
    (net (code "186") (name "unconnected-(IC36-NC-Pad5)") (class "Default")
      (node (ref "IC36") (pin "5") (pinfunction "NC_5") (pintype "passive"))
    )
    (net (code "187") (name "unconnected-(J1-Pad2)") (class "Default")
      (node (ref "J1") (pin "2") (pinfunction "2_2") (pintype "bidirectional"))
    )
    (net (code "188") (name "unconnected-(J2-Pad2)") (class "Default")
      (node (ref "J2") (pin "2") (pinfunction "2_2") (pintype "bidirectional"))
    )
    (net (code "189") (name "unconnected-(J49-Pada3)") (class "Default")
      (node (ref "J49") (pin "a3") (pinfunction "a3_a3") (pintype "bidirectional"))
    )
    (net (code "190") (name "unconnected-(J49-Pada5)") (class "Default")
      (node (ref "J49") (pin "a5") (pinfunction "a5_a5") (pintype "bidirectional"))
    )
    (net (code "191") (name "unconnected-(J49-Pada6)") (class "Default")
      (node (ref "J49") (pin "a6") (pinfunction "a6_a6") (pintype "bidirectional"))
    )
    (net (code "192") (name "unconnected-(J49-Pada7)") (class "Default")
      (node (ref "J49") (pin "a7") (pinfunction "a7_a7") (pintype "bidirectional"))
    )
    (net (code "193") (name "unconnected-(J49-Pada8)") (class "Default")
      (node (ref "J49") (pin "a8") (pinfunction "a8_a8") (pintype "bidirectional"))
    )
    (net (code "194") (name "unconnected-(J49-Pada9)") (class "Default")
      (node (ref "J49") (pin "a9") (pinfunction "a9_a9") (pintype "bidirectional"))
    )
    (net (code "195") (name "unconnected-(J49-Pada10)") (class "Default")
      (node (ref "J49") (pin "a10") (pinfunction "a10_a10") (pintype "bidirectional"))
    )
    (net (code "196") (name "unconnected-(J49-Pada12)") (class "Default")
      (node (ref "J49") (pin "a12") (pinfunction "a12_a12") (pintype "bidirectional"))
    )
    (net (code "197") (name "unconnected-(J49-Pada13)") (class "Default")
      (node (ref "J49") (pin "a13") (pinfunction "a13_a13") (pintype "bidirectional"))
    )
    (net (code "198") (name "unconnected-(J49-Pada14)") (class "Default")
      (node (ref "J49") (pin "a14") (pinfunction "a14_a14") (pintype "bidirectional"))
    )
    (net (code "199") (name "unconnected-(J49-Pada15)") (class "Default")
      (node (ref "J49") (pin "a15") (pinfunction "a15_a15") (pintype "bidirectional"))
    )
    (net (code "200") (name "unconnected-(J49-Pada16)") (class "Default")
      (node (ref "J49") (pin "a16") (pinfunction "a16_a16") (pintype "bidirectional"))
    )
    (net (code "201") (name "unconnected-(J49-Pada17)") (class "Default")
      (node (ref "J49") (pin "a17") (pinfunction "a17_a17") (pintype "bidirectional"))
    )
    (net (code "202") (name "unconnected-(J49-Pada19)") (class "Default")
      (node (ref "J49") (pin "a19") (pinfunction "a19_a19") (pintype "bidirectional"))
    )
    (net (code "203") (name "unconnected-(J49-Pada20)") (class "Default")
      (node (ref "J49") (pin "a20") (pinfunction "a20_a20") (pintype "bidirectional"))
    )
    (net (code "204") (name "unconnected-(J49-Pada21)") (class "Default")
      (node (ref "J49") (pin "a21") (pinfunction "a21_a21") (pintype "bidirectional"))
    )
    (net (code "205") (name "unconnected-(J49-Pada22)") (class "Default")
      (node (ref "J49") (pin "a22") (pinfunction "a22_a22") (pintype "bidirectional"))
    )
    (net (code "206") (name "unconnected-(J49-Pada23)") (class "Default")
      (node (ref "J49") (pin "a23") (pinfunction "a23_a23") (pintype "bidirectional"))
    )
    (net (code "207") (name "unconnected-(J49-Pada24)") (class "Default")
      (node (ref "J49") (pin "a24") (pinfunction "a24_a24") (pintype "bidirectional"))
    )
    (net (code "208") (name "unconnected-(J49-Pada26)") (class "Default")
      (node (ref "J49") (pin "a26") (pinfunction "a26_a26") (pintype "bidirectional"))
    )
    (net (code "209") (name "unconnected-(J49-Pada27)") (class "Default")
      (node (ref "J49") (pin "a27") (pinfunction "a27_a27") (pintype "bidirectional"))
    )
    (net (code "210") (name "unconnected-(J49-Pada28)") (class "Default")
      (node (ref "J49") (pin "a28") (pinfunction "a28_a28") (pintype "bidirectional"))
    )
    (net (code "211") (name "unconnected-(J49-Pada29)") (class "Default")
      (node (ref "J49") (pin "a29") (pinfunction "a29_a29") (pintype "bidirectional"))
    )
    (net (code "212") (name "unconnected-(J49-Pada30)") (class "Default")
      (node (ref "J49") (pin "a30") (pinfunction "a30_a30") (pintype "bidirectional"))
    )
    (net (code "213") (name "unconnected-(J49-Pada31)") (class "Default")
      (node (ref "J49") (pin "a31") (pinfunction "a31_a31") (pintype "bidirectional"))
    )
    (net (code "214") (name "unconnected-(J49-Padb3)") (class "Default")
      (node (ref "J49") (pin "b3") (pinfunction "b3_b3") (pintype "bidirectional"))
    )
    (net (code "215") (name "unconnected-(J49-Padb5)") (class "Default")
      (node (ref "J49") (pin "b5") (pinfunction "b5_b5") (pintype "bidirectional"))
    )
    (net (code "216") (name "unconnected-(J49-Padb6)") (class "Default")
      (node (ref "J49") (pin "b6") (pinfunction "b6_b6") (pintype "bidirectional"))
    )
    (net (code "217") (name "unconnected-(J49-Padb7)") (class "Default")
      (node (ref "J49") (pin "b7") (pinfunction "b7_b7") (pintype "bidirectional"))
    )
    (net (code "218") (name "unconnected-(J49-Padb8)") (class "Default")
      (node (ref "J49") (pin "b8") (pinfunction "b8_b8") (pintype "bidirectional"))
    )
    (net (code "219") (name "unconnected-(J49-Padb9)") (class "Default")
      (node (ref "J49") (pin "b9") (pinfunction "b9_b9") (pintype "bidirectional"))
    )
    (net (code "220") (name "unconnected-(J49-Padb10)") (class "Default")
      (node (ref "J49") (pin "b10") (pinfunction "b10_b10") (pintype "bidirectional"))
    )
    (net (code "221") (name "unconnected-(J49-Padb12)") (class "Default")
      (node (ref "J49") (pin "b12") (pinfunction "b12_b12") (pintype "bidirectional"))
    )
    (net (code "222") (name "unconnected-(J49-Padb13)") (class "Default")
      (node (ref "J49") (pin "b13") (pinfunction "b13_b13") (pintype "bidirectional"))
    )
    (net (code "223") (name "unconnected-(J49-Padb14)") (class "Default")
      (node (ref "J49") (pin "b14") (pinfunction "b14_b14") (pintype "bidirectional"))
    )
    (net (code "224") (name "unconnected-(J49-Padb15)") (class "Default")
      (node (ref "J49") (pin "b15") (pinfunction "b15_b15") (pintype "bidirectional"))
    )
    (net (code "225") (name "unconnected-(J49-Padb16)") (class "Default")
      (node (ref "J49") (pin "b16") (pinfunction "b16_b16") (pintype "bidirectional"))
    )
    (net (code "226") (name "unconnected-(J49-Padb17)") (class "Default")
      (node (ref "J49") (pin "b17") (pinfunction "b17_b17") (pintype "bidirectional"))
    )
    (net (code "227") (name "unconnected-(J49-Padb19)") (class "Default")
      (node (ref "J49") (pin "b19") (pinfunction "b19_b19") (pintype "bidirectional"))
    )
    (net (code "228") (name "unconnected-(J49-Padb20)") (class "Default")
      (node (ref "J49") (pin "b20") (pinfunction "b20_b20") (pintype "bidirectional"))
    )
    (net (code "229") (name "unconnected-(J49-Padb21)") (class "Default")
      (node (ref "J49") (pin "b21") (pinfunction "b21_b21") (pintype "bidirectional"))
    )
    (net (code "230") (name "unconnected-(J49-Padb22)") (class "Default")
      (node (ref "J49") (pin "b22") (pinfunction "b22_b22") (pintype "bidirectional"))
    )
    (net (code "231") (name "unconnected-(J49-Padb23)") (class "Default")
      (node (ref "J49") (pin "b23") (pinfunction "b23_b23") (pintype "bidirectional"))
    )
    (net (code "232") (name "unconnected-(J49-Padb24)") (class "Default")
      (node (ref "J49") (pin "b24") (pinfunction "b24_b24") (pintype "bidirectional"))
    )
    (net (code "233") (name "unconnected-(J49-Padb26)") (class "Default")
      (node (ref "J49") (pin "b26") (pinfunction "b26_b26") (pintype "bidirectional"))
    )
    (net (code "234") (name "unconnected-(J49-Padb27)") (class "Default")
      (node (ref "J49") (pin "b27") (pinfunction "b27_b27") (pintype "bidirectional"))
    )
    (net (code "235") (name "unconnected-(J49-Padb28)") (class "Default")
      (node (ref "J49") (pin "b28") (pinfunction "b28_b28") (pintype "bidirectional"))
    )
    (net (code "236") (name "unconnected-(J49-Padb29)") (class "Default")
      (node (ref "J49") (pin "b29") (pinfunction "b29_b29") (pintype "bidirectional"))
    )
    (net (code "237") (name "unconnected-(J49-Padb30)") (class "Default")
      (node (ref "J49") (pin "b30") (pinfunction "b30_b30") (pintype "bidirectional"))
    )
    (net (code "238") (name "unconnected-(J49-Padb31)") (class "Default")
      (node (ref "J49") (pin "b31") (pinfunction "b31_b31") (pintype "bidirectional"))
    )
    (net (code "239") (name "unconnected-(J49-Padc3)") (class "Default")
      (node (ref "J49") (pin "c3") (pinfunction "c3_c3") (pintype "bidirectional"))
    )
    (net (code "240") (name "unconnected-(J49-Padc5)") (class "Default")
      (node (ref "J49") (pin "c5") (pinfunction "c5_c5") (pintype "bidirectional"))
    )
    (net (code "241") (name "unconnected-(J49-Padc6)") (class "Default")
      (node (ref "J49") (pin "c6") (pinfunction "c6_c6") (pintype "bidirectional"))
    )
    (net (code "242") (name "unconnected-(J49-Padc7)") (class "Default")
      (node (ref "J49") (pin "c7") (pinfunction "c7_c7") (pintype "bidirectional"))
    )
    (net (code "243") (name "unconnected-(J49-Padc8)") (class "Default")
      (node (ref "J49") (pin "c8") (pinfunction "c8_c8") (pintype "bidirectional"))
    )
    (net (code "244") (name "unconnected-(J49-Padc9)") (class "Default")
      (node (ref "J49") (pin "c9") (pinfunction "c9_c9") (pintype "bidirectional"))
    )
    (net (code "245") (name "unconnected-(J49-Padc10)") (class "Default")
      (node (ref "J49") (pin "c10") (pinfunction "c10_c10") (pintype "bidirectional"))
    )
    (net (code "246") (name "unconnected-(J49-Padc12)") (class "Default")
      (node (ref "J49") (pin "c12") (pinfunction "c12_c12") (pintype "bidirectional"))
    )
    (net (code "247") (name "unconnected-(J49-Padc13)") (class "Default")
      (node (ref "J49") (pin "c13") (pinfunction "c13_c13") (pintype "bidirectional"))
    )
    (net (code "248") (name "unconnected-(J49-Padc14)") (class "Default")
      (node (ref "J49") (pin "c14") (pinfunction "c14_c14") (pintype "bidirectional"))
    )
    (net (code "249") (name "unconnected-(J49-Padc15)") (class "Default")
      (node (ref "J49") (pin "c15") (pinfunction "c15_c15") (pintype "bidirectional"))
    )
    (net (code "250") (name "unconnected-(J49-Padc16)") (class "Default")
      (node (ref "J49") (pin "c16") (pinfunction "c16_c16") (pintype "bidirectional"))
    )
    (net (code "251") (name "unconnected-(J49-Padc17)") (class "Default")
      (node (ref "J49") (pin "c17") (pinfunction "c17_c17") (pintype "bidirectional"))
    )
    (net (code "252") (name "unconnected-(J49-Padc19)") (class "Default")
      (node (ref "J49") (pin "c19") (pinfunction "c19_c19") (pintype "bidirectional"))
    )
    (net (code "253") (name "unconnected-(J49-Padc20)") (class "Default")
      (node (ref "J49") (pin "c20") (pinfunction "c20_c20") (pintype "bidirectional"))
    )
    (net (code "254") (name "unconnected-(J49-Padc21)") (class "Default")
      (node (ref "J49") (pin "c21") (pinfunction "c21_c21") (pintype "bidirectional"))
    )
    (net (code "255") (name "unconnected-(J49-Padc22)") (class "Default")
      (node (ref "J49") (pin "c22") (pinfunction "c22_c22") (pintype "bidirectional"))
    )
    (net (code "256") (name "unconnected-(J49-Padc23)") (class "Default")
      (node (ref "J49") (pin "c23") (pinfunction "c23_c23") (pintype "bidirectional"))
    )
    (net (code "257") (name "unconnected-(J49-Padc24)") (class "Default")
      (node (ref "J49") (pin "c24") (pinfunction "c24_c24") (pintype "bidirectional"))
    )
    (net (code "258") (name "unconnected-(J49-Padc26)") (class "Default")
      (node (ref "J49") (pin "c26") (pinfunction "c26_c26") (pintype "bidirectional"))
    )
    (net (code "259") (name "unconnected-(J49-Padc27)") (class "Default")
      (node (ref "J49") (pin "c27") (pinfunction "c27_c27") (pintype "bidirectional"))
    )
    (net (code "260") (name "unconnected-(J49-Padc28)") (class "Default")
      (node (ref "J49") (pin "c28") (pinfunction "c28_c28") (pintype "bidirectional"))
    )
    (net (code "261") (name "unconnected-(J49-Padc29)") (class "Default")
      (node (ref "J49") (pin "c29") (pinfunction "c29_c29") (pintype "bidirectional"))
    )
    (net (code "262") (name "unconnected-(J49-Padc30)") (class "Default")
      (node (ref "J49") (pin "c30") (pinfunction "c30_c30") (pintype "bidirectional"))
    )
    (net (code "263") (name "unconnected-(J49-Padc31)") (class "Default")
      (node (ref "J49") (pin "c31") (pinfunction "c31_c31") (pintype "bidirectional"))
    )
  )
)
